# octanis_eps.net
KiCad netlist of a schematic drawn in EAGLE
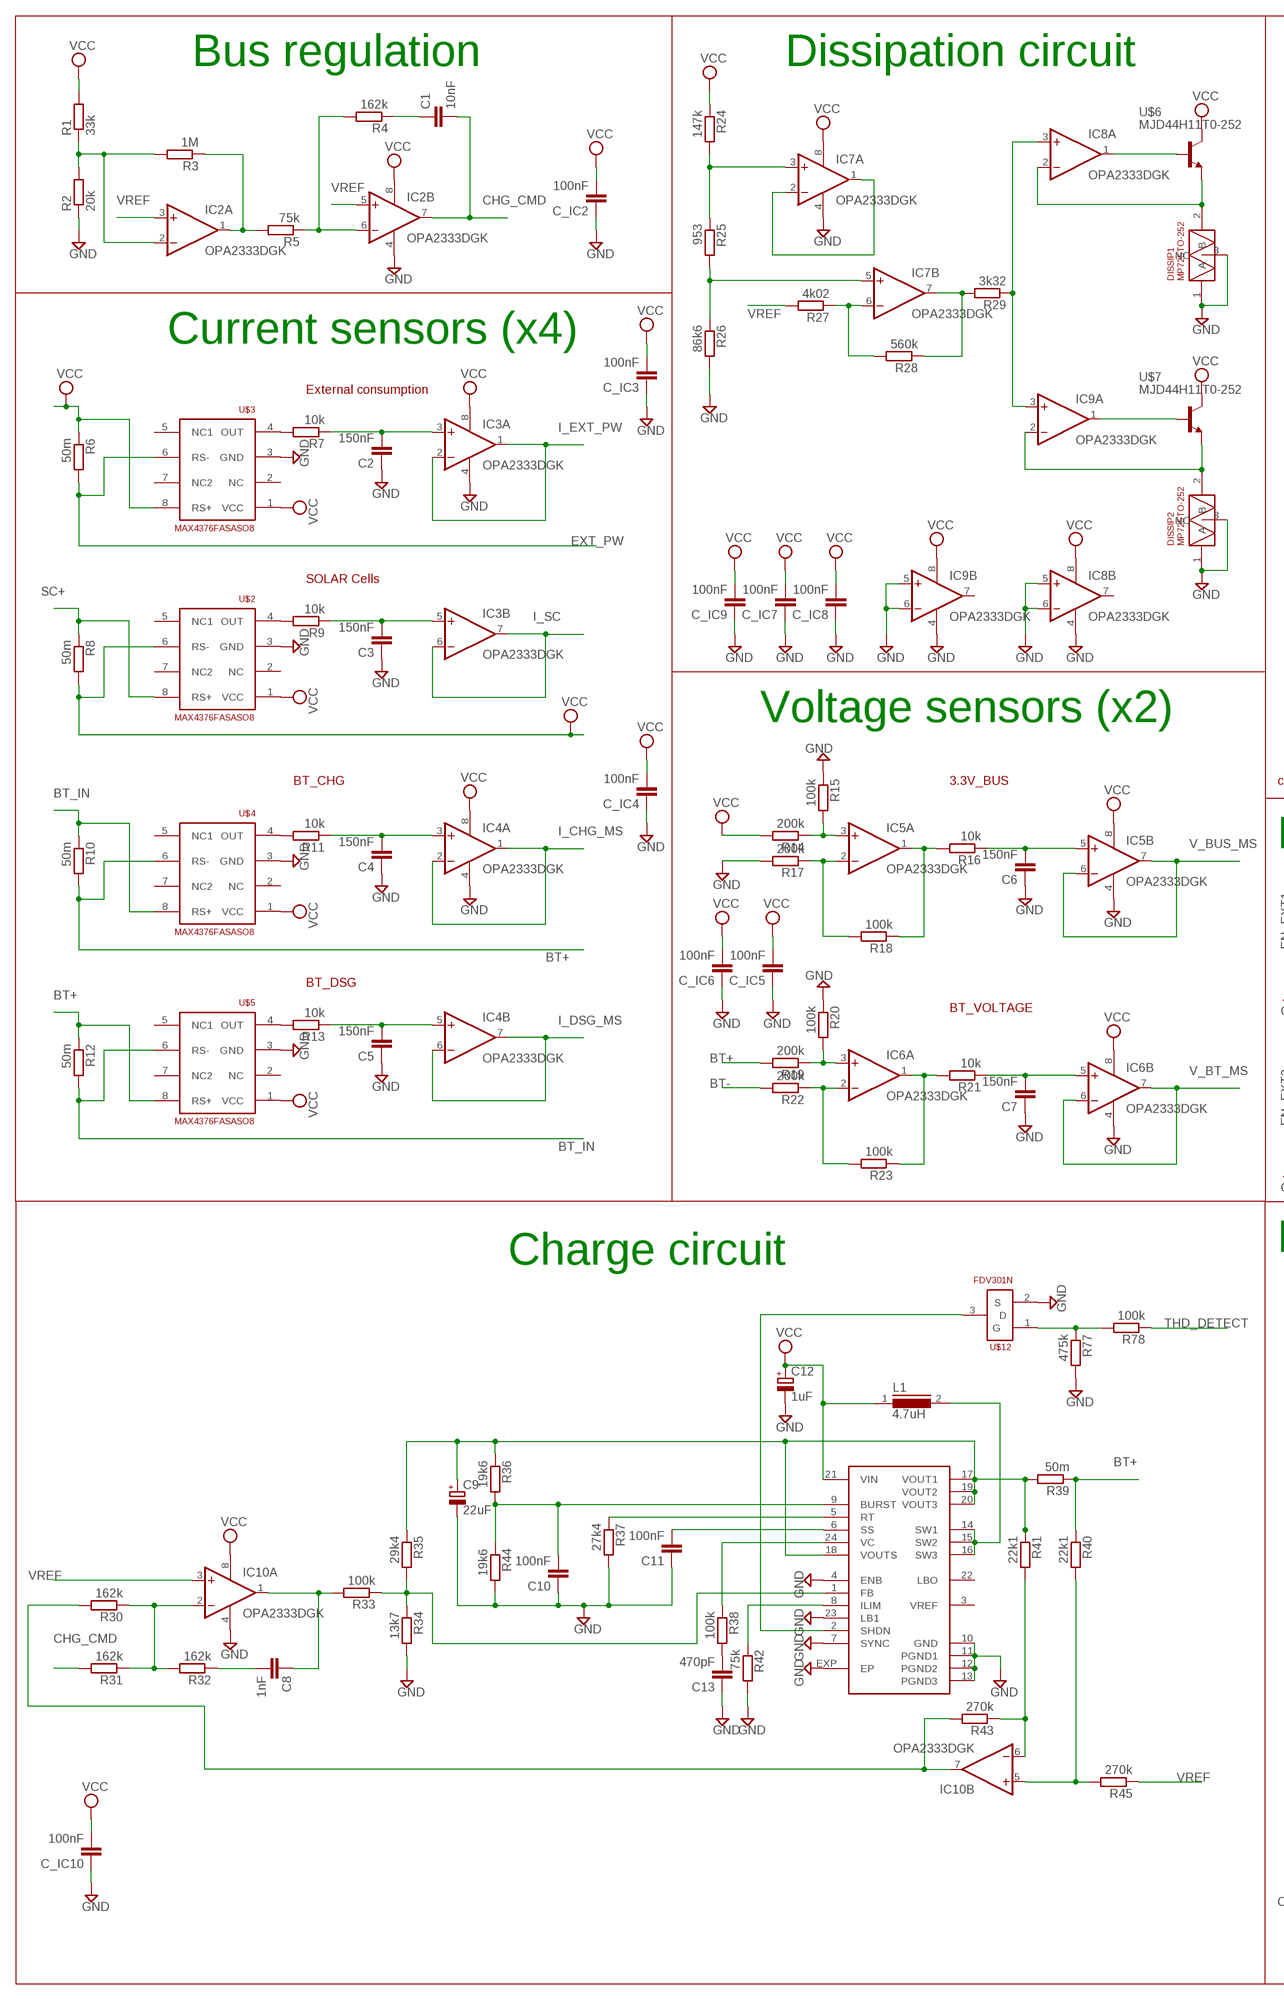
[diagram p0: schematic, sheet 1, part 1 of 2]
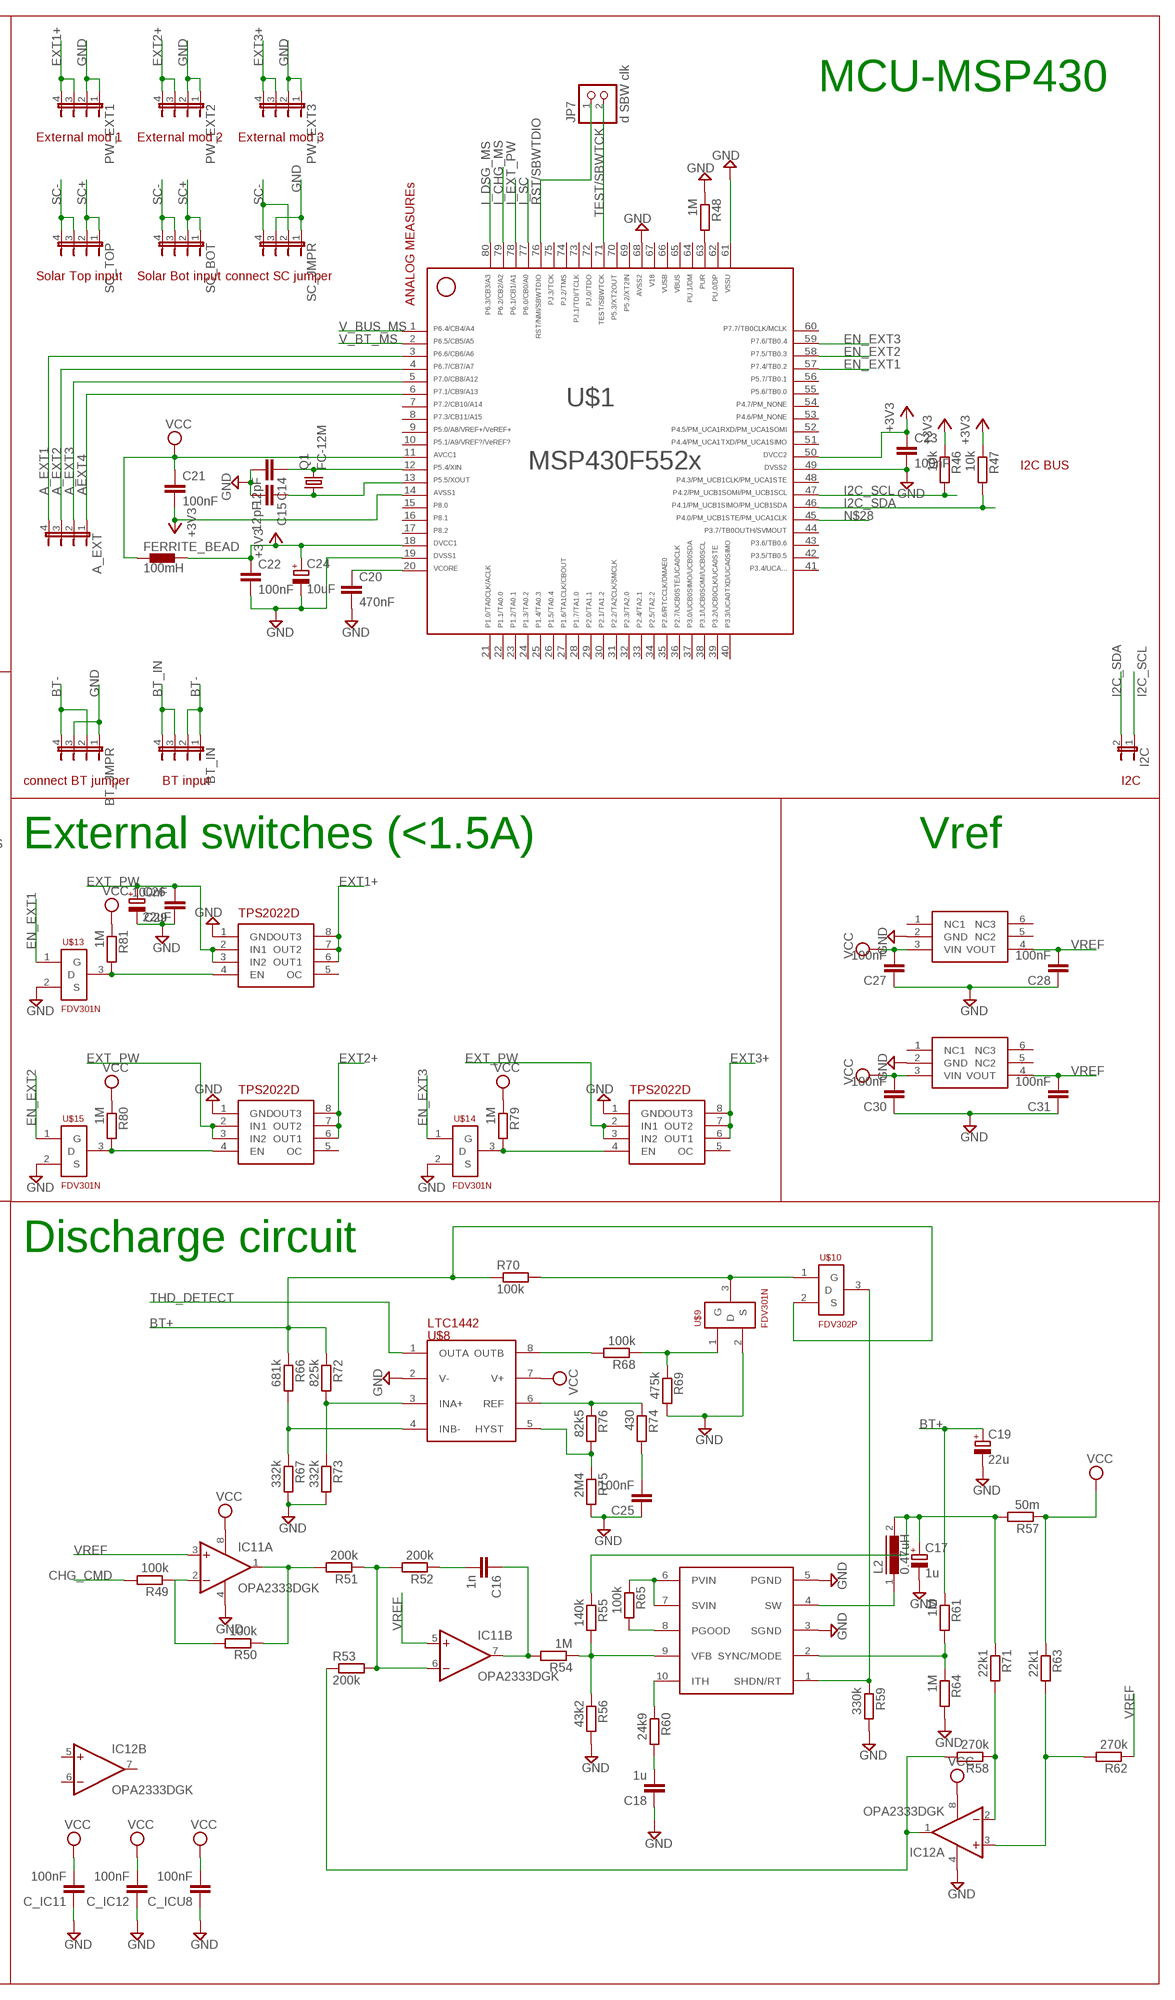
[diagram p1: schematic, sheet 1, part 2 of 2]

(export (version "E")
  (design (tool "Eeschema 10.0.6"))
  (components
    (comp (ref "A_EXT")
      (value "JP4E")
      (footprint "eagle-import:JP4")
      (libsource (lib "eagle-import") (part "JP4E"))
    )
    (comp (ref "BT_IN")
      (value "JP4E")
      (footprint "eagle-import:JP4")
      (libsource (lib "eagle-import") (part "JP4E"))
    )
    (comp (ref "BT_JMPR")
      (value "JP4E")
      (footprint "eagle-import:JP4")
      (libsource (lib "eagle-import") (part "JP4E"))
    )
    (comp (ref "C1")
      (value "10nF")
      (footprint "eagle-import:C0603")
      (libsource (lib "eagle-import") (part "C-EUC0603"))
    )
    (comp (ref "C2")
      (value "150nF")
      (footprint "eagle-import:C0603")
      (libsource (lib "eagle-import") (part "C-EUC0603"))
    )
    (comp (ref "C3")
      (value "150nF")
      (footprint "eagle-import:C0603")
      (libsource (lib "eagle-import") (part "C-EUC0603"))
    )
    (comp (ref "C4")
      (value "150nF")
      (footprint "eagle-import:C0603")
      (libsource (lib "eagle-import") (part "C-EUC0603"))
    )
    (comp (ref "C5")
      (value "150nF")
      (footprint "eagle-import:C0603")
      (libsource (lib "eagle-import") (part "C-EUC0603"))
    )
    (comp (ref "C6")
      (value "150nF")
      (footprint "eagle-import:C0603")
      (libsource (lib "eagle-import") (part "C-EUC0603"))
    )
    (comp (ref "C7")
      (value "150nF")
      (footprint "eagle-import:C0603")
      (libsource (lib "eagle-import") (part "C-EUC0603"))
    )
    (comp (ref "C8")
      (value "1nF")
      (footprint "eagle-import:C0603")
      (libsource (lib "eagle-import") (part "C-EUC0603"))
    )
    (comp (ref "C9")
      (value "22uF")
      (footprint "eagle-import:A_3216-18R")
      (libsource (lib "eagle-import") (part "CPOL-EUA/3216-18R"))
    )
    (comp (ref "C10")
      (value "100nF")
      (footprint "eagle-import:C0603")
      (libsource (lib "eagle-import") (part "C-EUC0603"))
    )
    (comp (ref "C11")
      (value "100nF")
      (footprint "eagle-import:C0603")
      (libsource (lib "eagle-import") (part "C-EUC0603"))
    )
    (comp (ref "C12")
      (value "1uF")
      (footprint "eagle-import:A_3216-18R")
      (libsource (lib "eagle-import") (part "CPOL-EUA/3216-18R"))
    )
    (comp (ref "C13")
      (value "470pF")
      (footprint "eagle-import:C0603")
      (libsource (lib "eagle-import") (part "C-EUC0603"))
    )
    (comp (ref "C14")
      (value "12pF")
      (footprint "eagle-import:C0603")
      (libsource (lib "eagle-import") (part "C-EUC0603"))
    )
    (comp (ref "C15")
      (value "12pF")
      (footprint "eagle-import:C0603")
      (libsource (lib "eagle-import") (part "C-EUC0603"))
    )
    (comp (ref "C16")
      (value "1n")
      (footprint "eagle-import:C0603")
      (libsource (lib "eagle-import") (part "C-EUC0603"))
    )
    (comp (ref "C17")
      (value "1u")
      (footprint "eagle-import:A_3216-18R")
      (libsource (lib "eagle-import") (part "CPOL-EUA/3216-18R"))
    )
    (comp (ref "C18")
      (value "1u")
      (footprint "eagle-import:C0603")
      (libsource (lib "eagle-import") (part "C-EUC0603"))
    )
    (comp (ref "C19")
      (value "22u")
      (footprint "eagle-import:A_3216-18R")
      (libsource (lib "eagle-import") (part "CPOL-EUA/3216-18R"))
    )
    (comp (ref "C20")
      (value "470nF")
      (footprint "eagle-import:C0603")
      (libsource (lib "eagle-import") (part "C-EUC0603"))
    )
    (comp (ref "C21")
      (value "100nF")
      (footprint "eagle-import:C0603")
      (libsource (lib "eagle-import") (part "C-EUC0603"))
    )
    (comp (ref "C22")
      (value "100nF")
      (footprint "eagle-import:C0603")
      (libsource (lib "eagle-import") (part "C-EUC0603"))
    )
    (comp (ref "C23")
      (value "100nF")
      (footprint "eagle-import:C0603")
      (libsource (lib "eagle-import") (part "C-EUC0603"))
    )
    (comp (ref "C24")
      (value "10uF")
      (footprint "eagle-import:A_3216-18R")
      (libsource (lib "eagle-import") (part "CPOL-EUA/3216-18R"))
    )
    (comp (ref "C25")
      (value "100nF")
      (footprint "eagle-import:C0603")
      (libsource (lib "eagle-import") (part "C-EUC0603"))
    )
    (comp (ref "C26")
      (value "22uF")
      (footprint "eagle-import:A_3216-18R")
      (libsource (lib "eagle-import") (part "CPOL-EUA/3216-18R"))
    )
    (comp (ref "C27")
      (value "100nF")
      (footprint "eagle-import:C0603")
      (libsource (lib "eagle-import") (part "C-EUC0603"))
    )
    (comp (ref "C28")
      (value "100nF")
      (footprint "eagle-import:C0603")
      (libsource (lib "eagle-import") (part "C-EUC0603"))
    )
    (comp (ref "C29")
      (value "100nF")
      (footprint "eagle-import:C0603")
      (libsource (lib "eagle-import") (part "C-EUC0603"))
    )
    (comp (ref "C30")
      (value "100nF")
      (footprint "eagle-import:C0603")
      (libsource (lib "eagle-import") (part "C-EUC0603"))
    )
    (comp (ref "C31")
      (value "100nF")
      (footprint "eagle-import:C0603")
      (libsource (lib "eagle-import") (part "C-EUC0603"))
    )
    (comp (ref "C_IC2")
      (value "100nF")
      (footprint "eagle-import:C0603")
      (libsource (lib "eagle-import") (part "C-EUC0603"))
    )
    (comp (ref "C_IC3")
      (value "100nF")
      (footprint "eagle-import:C0603")
      (libsource (lib "eagle-import") (part "C-EUC0603"))
    )
    (comp (ref "C_IC4")
      (value "100nF")
      (footprint "eagle-import:C0603")
      (libsource (lib "eagle-import") (part "C-EUC0603"))
    )
    (comp (ref "C_IC5")
      (value "100nF")
      (footprint "eagle-import:C0603")
      (libsource (lib "eagle-import") (part "C-EUC0603"))
    )
    (comp (ref "C_IC6")
      (value "100nF")
      (footprint "eagle-import:C0603")
      (libsource (lib "eagle-import") (part "C-EUC0603"))
    )
    (comp (ref "C_IC7")
      (value "100nF")
      (footprint "eagle-import:C0603")
      (libsource (lib "eagle-import") (part "C-EUC0603"))
    )
    (comp (ref "C_IC8")
      (value "100nF")
      (footprint "eagle-import:C0603")
      (libsource (lib "eagle-import") (part "C-EUC0603"))
    )
    (comp (ref "C_IC9")
      (value "100nF")
      (footprint "eagle-import:C0603")
      (libsource (lib "eagle-import") (part "C-EUC0603"))
    )
    (comp (ref "C_IC10")
      (value "100nF")
      (footprint "eagle-import:C0603")
      (libsource (lib "eagle-import") (part "C-EUC0603"))
    )
    (comp (ref "C_IC11")
      (value "100nF")
      (footprint "eagle-import:C0603")
      (libsource (lib "eagle-import") (part "C-EUC0603"))
    )
    (comp (ref "C_IC12")
      (value "100nF")
      (footprint "eagle-import:C0603")
      (libsource (lib "eagle-import") (part "C-EUC0603"))
    )
    (comp (ref "C_ICU8")
      (value "100nF")
      (footprint "eagle-import:C0603")
      (libsource (lib "eagle-import") (part "C-EUC0603"))
    )
    (comp (ref "DISSIP1")
      (value "MP725TO-252")
      (footprint "eagle-import:TO252")
      (libsource (lib "eagle-import") (part "MP725TO-252"))
    )
    (comp (ref "DISSIP2")
      (value "MP725TO-252")
      (footprint "eagle-import:TO252")
      (libsource (lib "eagle-import") (part "MP725TO-252"))
    )
    (comp (ref "FERRITE_BEAD")
      (value "100mH")
      (footprint "eagle-import:0402")
      (libsource (lib "eagle-import") (part "BLM15HD601SN1"))
    )
    (comp (ref "I2C")
      (value "JP1E")
      (footprint "eagle-import:JP1")
      (libsource (lib "eagle-import") (part "JP1E"))
    )
    (comp (ref "IC2")
      (value "OPA2333DGK")
      (footprint "eagle-import:MSOP08")
      (libsource (lib "eagle-import") (part "OPA2333DGK"))
    )
    (comp (ref "IC3")
      (value "OPA2333DGK")
      (footprint "eagle-import:MSOP08")
      (libsource (lib "eagle-import") (part "OPA2333DGK"))
    )
    (comp (ref "IC4")
      (value "OPA2333DGK")
      (footprint "eagle-import:MSOP08")
      (libsource (lib "eagle-import") (part "OPA2333DGK"))
    )
    (comp (ref "IC5")
      (value "OPA2333DGK")
      (footprint "eagle-import:MSOP08")
      (libsource (lib "eagle-import") (part "OPA2333DGK"))
    )
    (comp (ref "IC6")
      (value "OPA2333DGK")
      (footprint "eagle-import:MSOP08")
      (libsource (lib "eagle-import") (part "OPA2333DGK"))
    )
    (comp (ref "IC7")
      (value "OPA2333DGK")
      (footprint "eagle-import:MSOP08")
      (libsource (lib "eagle-import") (part "OPA2333DGK"))
    )
    (comp (ref "IC8")
      (value "OPA2333DGK")
      (footprint "eagle-import:MSOP08")
      (libsource (lib "eagle-import") (part "OPA2333DGK"))
    )
    (comp (ref "IC9")
      (value "OPA2333DGK")
      (footprint "eagle-import:MSOP08")
      (libsource (lib "eagle-import") (part "OPA2333DGK"))
    )
    (comp (ref "IC10")
      (value "OPA2333DGK")
      (footprint "eagle-import:MSOP08")
      (libsource (lib "eagle-import") (part "OPA2333DGK"))
    )
    (comp (ref "IC11")
      (value "OPA2333DGK")
      (footprint "eagle-import:MSOP08")
      (libsource (lib "eagle-import") (part "OPA2333DGK"))
    )
    (comp (ref "IC12")
      (value "OPA2333DGK")
      (footprint "eagle-import:MSOP08")
      (libsource (lib "eagle-import") (part "OPA2333DGK"))
    )
    (comp (ref "JP7")
      (value "d SBW clk")
      (footprint "eagle-import:1X02")
      (libsource (lib "eagle-import") (part "PINHD-1X2"))
    )
    (comp (ref "L1")
      (value "4.7uH")
      (footprint "eagle-import:DR73")
      (libsource (lib "eagle-import") (part "DR73"))
    )
    (comp (ref "L2")
      (value "0.47uH")
      (footprint "eagle-import:DR73")
      (libsource (lib "eagle-import") (part "DR73"))
    )
    (comp (ref "LTC3411")
      (value "LT3411")
      (footprint "eagle-import:MSOP10")
      (libsource (lib "eagle-import") (part "LT3411"))
    )
    (comp (ref "PW_EXT1")
      (value "JP4E")
      (footprint "eagle-import:JP4")
      (libsource (lib "eagle-import") (part "JP4E"))
    )
    (comp (ref "PW_EXT2")
      (value "JP4E")
      (footprint "eagle-import:JP4")
      (libsource (lib "eagle-import") (part "JP4E"))
    )
    (comp (ref "PW_EXT3")
      (value "JP4E")
      (footprint "eagle-import:JP4")
      (libsource (lib "eagle-import") (part "JP4E"))
    )
    (comp (ref "Q1")
      (value "FC-12M")
      (footprint "eagle-import:FC-12M")
      (libsource (lib "eagle-import") (part "FC-12M"))
    )
    (comp (ref "R1")
      (value "33k")
      (footprint "eagle-import:R0603")
      (libsource (lib "eagle-import") (part "R-EU_R0603"))
    )
    (comp (ref "R2")
      (value "20k")
      (footprint "eagle-import:R0603")
      (libsource (lib "eagle-import") (part "R-EU_R0603"))
    )
    (comp (ref "R3")
      (value "1M")
      (footprint "eagle-import:R0603")
      (libsource (lib "eagle-import") (part "R-EU_R0603"))
    )
    (comp (ref "R4")
      (value "162k")
      (footprint "eagle-import:R0603")
      (libsource (lib "eagle-import") (part "R-EU_R0603"))
    )
    (comp (ref "R5")
      (value "75k")
      (footprint "eagle-import:R0603")
      (libsource (lib "eagle-import") (part "R-EU_R0603"))
    )
    (comp (ref "R6")
      (value "50m")
      (footprint "eagle-import:R1206")
      (libsource (lib "eagle-import") (part "R-EU_R1206"))
    )
    (comp (ref "R7")
      (value "10k")
      (footprint "eagle-import:R0603")
      (libsource (lib "eagle-import") (part "R-EU_R0603"))
    )
    (comp (ref "R8")
      (value "50m")
      (footprint "eagle-import:R1206")
      (libsource (lib "eagle-import") (part "R-EU_R1206"))
    )
    (comp (ref "R9")
      (value "10k")
      (footprint "eagle-import:R0603")
      (libsource (lib "eagle-import") (part "R-EU_R0603"))
    )
    (comp (ref "R10")
      (value "50m")
      (footprint "eagle-import:R1206")
      (libsource (lib "eagle-import") (part "R-EU_R1206"))
    )
    (comp (ref "R11")
      (value "10k")
      (footprint "eagle-import:R0603")
      (libsource (lib "eagle-import") (part "R-EU_R0603"))
    )
    (comp (ref "R12")
      (value "50m")
      (footprint "eagle-import:R1206")
      (libsource (lib "eagle-import") (part "R-EU_R1206"))
    )
    (comp (ref "R13")
      (value "10k")
      (footprint "eagle-import:R0603")
      (libsource (lib "eagle-import") (part "R-EU_R0603"))
    )
    (comp (ref "R14")
      (value "200k")
      (footprint "eagle-import:R0603")
      (libsource (lib "eagle-import") (part "R-EU_R0603"))
    )
    (comp (ref "R15")
      (value "100k")
      (footprint "eagle-import:R0603")
      (libsource (lib "eagle-import") (part "R-EU_R0603"))
    )
    (comp (ref "R16")
      (value "10k")
      (footprint "eagle-import:R0603")
      (libsource (lib "eagle-import") (part "R-EU_R0603"))
    )
    (comp (ref "R17")
      (value "200k")
      (footprint "eagle-import:R0603")
      (libsource (lib "eagle-import") (part "R-EU_R0603"))
    )
    (comp (ref "R18")
      (value "100k")
      (footprint "eagle-import:R0603")
      (libsource (lib "eagle-import") (part "R-EU_R0603"))
    )
    (comp (ref "R19")
      (value "200k")
      (footprint "eagle-import:R0603")
      (libsource (lib "eagle-import") (part "R-EU_R0603"))
    )
    (comp (ref "R20")
      (value "100k")
      (footprint "eagle-import:R0603")
      (libsource (lib "eagle-import") (part "R-EU_R0603"))
    )
    (comp (ref "R21")
      (value "10k")
      (footprint "eagle-import:R0603")
      (libsource (lib "eagle-import") (part "R-EU_R0603"))
    )
    (comp (ref "R22")
      (value "200k")
      (footprint "eagle-import:R0603")
      (libsource (lib "eagle-import") (part "R-EU_R0603"))
    )
    (comp (ref "R23")
      (value "100k")
      (footprint "eagle-import:R0603")
      (libsource (lib "eagle-import") (part "R-EU_R0603"))
    )
    (comp (ref "R24")
      (value "147k")
      (footprint "eagle-import:R0603")
      (libsource (lib "eagle-import") (part "R-EU_R0603"))
    )
    (comp (ref "R25")
      (value "953")
      (footprint "eagle-import:R0603")
      (libsource (lib "eagle-import") (part "R-EU_R0603"))
    )
    (comp (ref "R26")
      (value "86k6")
      (footprint "eagle-import:R0603")
      (libsource (lib "eagle-import") (part "R-EU_R0603"))
    )
    (comp (ref "R27")
      (value "4k02")
      (footprint "eagle-import:R0603")
      (libsource (lib "eagle-import") (part "R-EU_R0603"))
    )
    (comp (ref "R28")
      (value "560k")
      (footprint "eagle-import:R0603")
      (libsource (lib "eagle-import") (part "R-EU_R0603"))
    )
    (comp (ref "R29")
      (value "3k32")
      (footprint "eagle-import:R0603")
      (libsource (lib "eagle-import") (part "R-EU_R0603"))
    )
    (comp (ref "R30")
      (value "162k")
      (footprint "eagle-import:R0603")
      (libsource (lib "eagle-import") (part "R-EU_R0603"))
    )
    (comp (ref "R31")
      (value "162k")
      (footprint "eagle-import:R0603")
      (libsource (lib "eagle-import") (part "R-EU_R0603"))
    )
    (comp (ref "R32")
      (value "162k")
      (footprint "eagle-import:R0603")
      (libsource (lib "eagle-import") (part "R-EU_R0603"))
    )
    (comp (ref "R33")
      (value "100k")
      (footprint "eagle-import:R0603")
      (libsource (lib "eagle-import") (part "R-EU_R0603"))
    )
    (comp (ref "R34")
      (value "13k7")
      (footprint "eagle-import:R0603")
      (libsource (lib "eagle-import") (part "R-EU_R0603"))
    )
    (comp (ref "R35")
      (value "29k4")
      (footprint "eagle-import:R0603")
      (libsource (lib "eagle-import") (part "R-EU_R0603"))
    )
    (comp (ref "R36")
      (value "19k6")
      (footprint "eagle-import:R0603")
      (libsource (lib "eagle-import") (part "R-EU_R0603"))
    )
    (comp (ref "R37")
      (value "27k4")
      (footprint "eagle-import:R0603")
      (libsource (lib "eagle-import") (part "R-EU_R0603"))
    )
    (comp (ref "R38")
      (value "100k")
      (footprint "eagle-import:R0603")
      (libsource (lib "eagle-import") (part "R-EU_R0603"))
    )
    (comp (ref "R39")
      (value "50m")
      (footprint "eagle-import:R1206")
      (libsource (lib "eagle-import") (part "R-EU_R1206"))
    )
    (comp (ref "R40")
      (value "22k1")
      (footprint "eagle-import:R0603")
      (libsource (lib "eagle-import") (part "R-EU_R0603"))
    )
    (comp (ref "R41")
      (value "22k1")
      (footprint "eagle-import:R0603")
      (libsource (lib "eagle-import") (part "R-EU_R0603"))
    )
    (comp (ref "R42")
      (value "75k")
      (footprint "eagle-import:R0603")
      (libsource (lib "eagle-import") (part "R-EU_R0603"))
    )
    (comp (ref "R43")
      (value "270k")
      (footprint "eagle-import:R0603")
      (libsource (lib "eagle-import") (part "R-EU_R0603"))
    )
    (comp (ref "R44")
      (value "19k6")
      (footprint "eagle-import:R0603")
      (libsource (lib "eagle-import") (part "R-EU_R0603"))
    )
    (comp (ref "R45")
      (value "270k")
      (footprint "eagle-import:R0603")
      (libsource (lib "eagle-import") (part "R-EU_R0603"))
    )
    (comp (ref "R46")
      (value "10k")
      (footprint "eagle-import:R0603")
      (libsource (lib "eagle-import") (part "R-EU_R0603"))
    )
    (comp (ref "R47")
      (value "10k")
      (footprint "eagle-import:R0603")
      (libsource (lib "eagle-import") (part "R-EU_R0603"))
    )
    (comp (ref "R48")
      (value "1M")
      (footprint "eagle-import:R0603")
      (libsource (lib "eagle-import") (part "R-EU_R0603"))
    )
    (comp (ref "R49")
      (value "100k")
      (footprint "eagle-import:R0603")
      (libsource (lib "eagle-import") (part "R-EU_R0603"))
    )
    (comp (ref "R50")
      (value "100k")
      (footprint "eagle-import:R0603")
      (libsource (lib "eagle-import") (part "R-EU_R0603"))
    )
    (comp (ref "R51")
      (value "200k")
      (footprint "eagle-import:R0603")
      (libsource (lib "eagle-import") (part "R-EU_R0603"))
    )
    (comp (ref "R52")
      (value "200k")
      (footprint "eagle-import:R0603")
      (libsource (lib "eagle-import") (part "R-EU_R0603"))
    )
    (comp (ref "R53")
      (value "200k")
      (footprint "eagle-import:R0603")
      (libsource (lib "eagle-import") (part "R-EU_R0603"))
    )
    (comp (ref "R54")
      (value "1M")
      (footprint "eagle-import:R0603")
      (libsource (lib "eagle-import") (part "R-EU_R0603"))
    )
    (comp (ref "R55")
      (value "140k")
      (footprint "eagle-import:R0603")
      (libsource (lib "eagle-import") (part "R-EU_R0603"))
    )
    (comp (ref "R56")
      (value "43k2")
      (footprint "eagle-import:R0603")
      (libsource (lib "eagle-import") (part "R-EU_R0603"))
    )
    (comp (ref "R57")
      (value "50m")
      (footprint "eagle-import:R1206")
      (libsource (lib "eagle-import") (part "R-EU_R1206"))
    )
    (comp (ref "R58")
      (value "270k")
      (footprint "eagle-import:R0603")
      (libsource (lib "eagle-import") (part "R-EU_R0603"))
    )
    (comp (ref "R59")
      (value "330k")
      (footprint "eagle-import:R0603")
      (libsource (lib "eagle-import") (part "R-EU_R0603"))
    )
    (comp (ref "R60")
      (value "24k9")
      (footprint "eagle-import:R0603")
      (libsource (lib "eagle-import") (part "R-EU_R0603"))
    )
    (comp (ref "R61")
      (value "1M")
      (footprint "eagle-import:R0603")
      (libsource (lib "eagle-import") (part "R-EU_R0603"))
    )
    (comp (ref "R62")
      (value "270k")
      (footprint "eagle-import:R0603")
      (libsource (lib "eagle-import") (part "R-EU_R0603"))
    )
    (comp (ref "R63")
      (value "22k1")
      (footprint "eagle-import:R0603")
      (libsource (lib "eagle-import") (part "R-EU_R0603"))
    )
    (comp (ref "R64")
      (value "1M")
      (footprint "eagle-import:R0603")
      (libsource (lib "eagle-import") (part "R-EU_R0603"))
    )
    (comp (ref "R65")
      (value "100k")
      (footprint "eagle-import:R0603")
      (libsource (lib "eagle-import") (part "R-EU_R0603"))
    )
    (comp (ref "R66")
      (value "681k")
      (footprint "eagle-import:R0603")
      (libsource (lib "eagle-import") (part "R-EU_R0603"))
    )
    (comp (ref "R67")
      (value "332k")
      (footprint "eagle-import:R0603")
      (libsource (lib "eagle-import") (part "R-EU_R0603"))
    )
    (comp (ref "R68")
      (value "100k")
      (footprint "eagle-import:R0603")
      (libsource (lib "eagle-import") (part "R-EU_R0603"))
    )
    (comp (ref "R69")
      (value "475k")
      (footprint "eagle-import:R0603")
      (libsource (lib "eagle-import") (part "R-EU_R0603"))
    )
    (comp (ref "R70")
      (value "100k")
      (footprint "eagle-import:R0603")
      (libsource (lib "eagle-import") (part "R-EU_R0603"))
    )
    (comp (ref "R71")
      (value "22k1")
      (footprint "eagle-import:R0603")
      (libsource (lib "eagle-import") (part "R-EU_R0603"))
    )
    (comp (ref "R72")
      (value "825k")
      (footprint "eagle-import:R0603")
      (libsource (lib "eagle-import") (part "R-EU_R0603"))
    )
    (comp (ref "R73")
      (value "332k")
      (footprint "eagle-import:R0603")
      (libsource (lib "eagle-import") (part "R-EU_R0603"))
    )
    (comp (ref "R74")
      (value "430")
      (footprint "eagle-import:R0603")
      (libsource (lib "eagle-import") (part "R-EU_R0603"))
    )
    (comp (ref "R75")
      (value "2M4")
      (footprint "eagle-import:R0603")
      (libsource (lib "eagle-import") (part "R-EU_R0603"))
    )
    (comp (ref "R76")
      (value "82k5")
      (footprint "eagle-import:R0603")
      (libsource (lib "eagle-import") (part "R-EU_R0603"))
    )
    (comp (ref "R77")
      (value "475k")
      (footprint "eagle-import:R0603")
      (libsource (lib "eagle-import") (part "R-EU_R0603"))
    )
    (comp (ref "R78")
      (value "100k")
      (footprint "eagle-import:R0603")
      (libsource (lib "eagle-import") (part "R-EU_R0603"))
    )
    (comp (ref "R79")
      (value "1M")
      (footprint "eagle-import:R0603")
      (libsource (lib "eagle-import") (part "R-EU_R0603"))
    )
    (comp (ref "R80")
      (value "1M")
      (footprint "eagle-import:R0603")
      (libsource (lib "eagle-import") (part "R-EU_R0603"))
    )
    (comp (ref "R81")
      (value "1M")
      (footprint "eagle-import:R0603")
      (libsource (lib "eagle-import") (part "R-EU_R0603"))
    )
    (comp (ref "SC_BOT")
      (value "JP4E")
      (footprint "eagle-import:JP4")
      (libsource (lib "eagle-import") (part "JP4E"))
    )
    (comp (ref "SC_JMPR")
      (value "JP4E")
      (footprint "eagle-import:JP4")
      (libsource (lib "eagle-import") (part "JP4E"))
    )
    (comp (ref "SC_TOP")
      (value "JP4E")
      (footprint "eagle-import:JP4")
      (libsource (lib "eagle-import") (part "JP4E"))
    )
    (comp (ref "U$1")
      (value "F552X---PN80")
      (footprint "eagle-import:PN80")
      (libsource (lib "eagle-import") (part "F552X---PN80"))
    )
    (comp (ref "U$2")
      (value "MAX4376FASASO8")
      (footprint "eagle-import:SO8")
      (libsource (lib "eagle-import") (part "MAX4376FASASO8"))
    )
    (comp (ref "U$3")
      (value "MAX4376FASASO8")
      (footprint "eagle-import:SO8")
      (libsource (lib "eagle-import") (part "MAX4376FASASO8"))
    )
    (comp (ref "U$4")
      (value "MAX4376FASASO8")
      (footprint "eagle-import:SO8")
      (libsource (lib "eagle-import") (part "MAX4376FASASO8"))
    )
    (comp (ref "U$5")
      (value "MAX4376FASASO8")
      (footprint "eagle-import:SO8")
      (libsource (lib "eagle-import") (part "MAX4376FASASO8"))
    )
    (comp (ref "U$6")
      (value "MJD44H11T0-252")
      (footprint "eagle-import:TO252")
      (libsource (lib "eagle-import") (part "MJD44H11T0-252"))
    )
    (comp (ref "U$7")
      (value "MJD44H11T0-252")
      (footprint "eagle-import:TO252")
      (libsource (lib "eagle-import") (part "MJD44H11T0-252"))
    )
    (comp (ref "U$8")
      (value "LTC1442")
      (footprint "eagle-import:SO8")
      (libsource (lib "eagle-import") (part "LTC1442"))
    )
    (comp (ref "U$9")
      (value "FDV301N")
      (footprint "eagle-import:SOT23")
      (libsource (lib "eagle-import") (part "FDV301N"))
    )
    (comp (ref "U$10")
      (value "FDV302P")
      (footprint "eagle-import:SOT23")
      (libsource (lib "eagle-import") (part "FDV302P"))
    )
    (comp (ref "U$11")
      (value "LTC3421")
      (footprint "eagle-import:QFN24")
      (libsource (lib "eagle-import") (part "LTC3421"))
    )
    (comp (ref "U$12")
      (value "FDV301N")
      (footprint "eagle-import:SOT23")
      (libsource (lib "eagle-import") (part "FDV301N"))
    )
    (comp (ref "U$13")
      (value "FDV301N")
      (footprint "eagle-import:SOT23")
      (libsource (lib "eagle-import") (part "FDV301N"))
    )
    (comp (ref "U$14")
      (value "FDV301N")
      (footprint "eagle-import:SOT23")
      (libsource (lib "eagle-import") (part "FDV301N"))
    )
    (comp (ref "U$15")
      (value "FDV301N")
      (footprint "eagle-import:SOT23")
      (libsource (lib "eagle-import") (part "FDV301N"))
    )
    (comp (ref "U$16")
      (value "TPS2022D")
      (footprint "eagle-import:SO8")
      (libsource (lib "eagle-import") (part "TPS2022D"))
    )
    (comp (ref "U$17")
      (value "TPS2022D")
      (footprint "eagle-import:SO8")
      (libsource (lib "eagle-import") (part "TPS2022D"))
    )
    (comp (ref "U$18")
      (value "TPS2022D")
      (footprint "eagle-import:SO8")
      (libsource (lib "eagle-import") (part "TPS2022D"))
    )
    (comp (ref "U$19")
      (value "ADR127B")
      (footprint "eagle-import:TSOT23-6")
      (libsource (lib "eagle-import") (part "ADR127B"))
    )
    (comp (ref "U$20")
      (value "ADR127B")
      (footprint "eagle-import:TSOT23-6")
      (libsource (lib "eagle-import") (part "ADR127B"))
    )
  )
  (nets
    (net (code "1") (name "+3V3") (class "Default")
      (node (ref "C21") (pin "2") (pinfunction "2_2") (pintype "passive"))
      (node (ref "C22") (pin "1") (pinfunction "1_1") (pintype "passive"))
      (node (ref "C23") (pin "1") (pinfunction "1_1") (pintype "passive"))
      (node (ref "C24") (pin "+") (pinfunction "+_+") (pintype "passive"))
      (node (ref "FERRITE_BEAD") (pin "2") (pinfunction "2_2") (pintype "passive"))
      (node (ref "R46") (pin "1") (pinfunction "1_1") (pintype "passive"))
      (node (ref "R47") (pin "1") (pinfunction "1_1") (pintype "passive"))
      (node (ref "U$1") (pin "14") (pinfunction "14_14") (pintype "power_in"))
      (node (ref "U$1") (pin "18") (pinfunction "18_18") (pintype "power_in"))
      (node (ref "U$1") (pin "50") (pinfunction "50_50") (pintype "power_in"))
    )
    (net (code "2") (name "/65") (class "Default")
      (node (ref "U$1") (pin "65") (pinfunction "65_65") (pintype "power_in"))
    )
    (net (code "3") (name "/66") (class "Default")
      (node (ref "U$1") (pin "66") (pinfunction "66_66") (pintype "power_in"))
    )
    (net (code "4") (name "/67") (class "Default")
      (node (ref "U$1") (pin "67") (pinfunction "67_67") (pintype "power_in"))
    )
    (net (code "5") (name "/AEXT4") (class "Default")
      (node (ref "A_EXT") (pin "1") (pinfunction "1_1") (pintype "passive"))
      (node (ref "U$1") (pin "6") (pinfunction "6_6") (pintype "bidirectional"))
    )
    (net (code "6") (name "/A_EXT1") (class "Default")
      (node (ref "A_EXT") (pin "4") (pinfunction "4_4") (pintype "passive"))
      (node (ref "U$1") (pin "3") (pinfunction "3_3") (pintype "bidirectional"))
    )
    (net (code "7") (name "/A_EXT2") (class "Default")
      (node (ref "A_EXT") (pin "3") (pinfunction "3_3") (pintype "passive"))
      (node (ref "U$1") (pin "4") (pinfunction "4_4") (pintype "bidirectional"))
    )
    (net (code "8") (name "/A_EXT3") (class "Default")
      (node (ref "A_EXT") (pin "2") (pinfunction "2_2") (pintype "passive"))
      (node (ref "U$1") (pin "5") (pinfunction "5_5") (pintype "bidirectional"))
    )
    (net (code "9") (name "/BT+") (class "Default")
      (node (ref "C19") (pin "+") (pinfunction "+_+") (pintype "passive"))
      (node (ref "R10") (pin "2") (pinfunction "2_2") (pintype "passive"))
      (node (ref "R12") (pin "1") (pinfunction "1_1") (pintype "passive"))
      (node (ref "R19") (pin "2") (pinfunction "2_2") (pintype "passive"))
      (node (ref "R39") (pin "1") (pinfunction "1_1") (pintype "passive"))
      (node (ref "R40") (pin "1") (pinfunction "1_1") (pintype "passive"))
      (node (ref "R61") (pin "1") (pinfunction "1_1") (pintype "passive"))
      (node (ref "R66") (pin "1") (pinfunction "1_1") (pintype "passive"))
      (node (ref "R70") (pin "1") (pinfunction "1_1") (pintype "passive"))
      (node (ref "R72") (pin "1") (pinfunction "1_1") (pintype "passive"))
      (node (ref "U$10") (pin "2") (pinfunction "S_2") (pintype "bidirectional"))
      (node (ref "U$4") (pin "6") (pinfunction "RS-_6") (pintype "bidirectional"))
      (node (ref "U$5") (pin "8") (pinfunction "RS+_8") (pintype "bidirectional"))
    )
    (net (code "10") (name "/BT-") (class "Default")
      (node (ref "BT_IN") (pin "1") (pinfunction "1_1") (pintype "passive"))
      (node (ref "BT_IN") (pin "2") (pinfunction "2_2") (pintype "passive"))
      (node (ref "BT_JMPR") (pin "2") (pinfunction "2_2") (pintype "passive"))
      (node (ref "BT_JMPR") (pin "4") (pinfunction "4_4") (pintype "passive"))
      (node (ref "R22") (pin "2") (pinfunction "2_2") (pintype "passive"))
    )
    (net (code "11") (name "/BT_IN") (class "Default")
      (node (ref "BT_IN") (pin "3") (pinfunction "3_3") (pintype "passive"))
      (node (ref "BT_IN") (pin "4") (pinfunction "4_4") (pintype "passive"))
      (node (ref "R10") (pin "1") (pinfunction "1_1") (pintype "passive"))
      (node (ref "R12") (pin "2") (pinfunction "2_2") (pintype "passive"))
      (node (ref "U$4") (pin "8") (pinfunction "RS+_8") (pintype "bidirectional"))
      (node (ref "U$5") (pin "6") (pinfunction "RS-_6") (pintype "bidirectional"))
    )
    (net (code "12") (name "/CHG_CMD") (class "Default")
      (node (ref "C1") (pin "2") (pinfunction "2_2") (pintype "passive"))
      (node (ref "IC2") (pin "7") (pinfunction "OUT_7") (pintype "output"))
      (node (ref "R31") (pin "2") (pinfunction "2_2") (pintype "passive"))
      (node (ref "R49") (pin "2") (pinfunction "2_2") (pintype "passive"))
    )
    (net (code "13") (name "/EN_EXT1") (class "Default")
      (node (ref "U$1") (pin "57") (pinfunction "57_57") (pintype "bidirectional"))
      (node (ref "U$13") (pin "1") (pinfunction "G_1") (pintype "bidirectional"))
    )
    (net (code "14") (name "/EN_EXT2") (class "Default")
      (node (ref "U$1") (pin "58") (pinfunction "58_58") (pintype "bidirectional"))
      (node (ref "U$15") (pin "1") (pinfunction "G_1") (pintype "bidirectional"))
    )
    (net (code "15") (name "/EN_EXT3") (class "Default")
      (node (ref "U$1") (pin "59") (pinfunction "59_59") (pintype "bidirectional"))
      (node (ref "U$14") (pin "1") (pinfunction "G_1") (pintype "bidirectional"))
    )
    (net (code "16") (name "/EXT1+") (class "Default")
      (node (ref "PW_EXT1") (pin "3") (pinfunction "3_3") (pintype "passive"))
      (node (ref "PW_EXT1") (pin "4") (pinfunction "4_4") (pintype "passive"))
      (node (ref "U$16") (pin "6") (pinfunction "OUT1_6") (pintype "bidirectional"))
      (node (ref "U$16") (pin "7") (pinfunction "OUT2_7") (pintype "bidirectional"))
      (node (ref "U$16") (pin "8") (pinfunction "OUT3_8") (pintype "bidirectional"))
    )
    (net (code "17") (name "/EXT2+") (class "Default")
      (node (ref "PW_EXT2") (pin "3") (pinfunction "3_3") (pintype "passive"))
      (node (ref "PW_EXT2") (pin "4") (pinfunction "4_4") (pintype "passive"))
      (node (ref "U$17") (pin "6") (pinfunction "OUT1_6") (pintype "bidirectional"))
      (node (ref "U$17") (pin "7") (pinfunction "OUT2_7") (pintype "bidirectional"))
      (node (ref "U$17") (pin "8") (pinfunction "OUT3_8") (pintype "bidirectional"))
    )
    (net (code "18") (name "/EXT3+") (class "Default")
      (node (ref "PW_EXT3") (pin "3") (pinfunction "3_3") (pintype "passive"))
      (node (ref "PW_EXT3") (pin "4") (pinfunction "4_4") (pintype "passive"))
      (node (ref "U$18") (pin "6") (pinfunction "OUT1_6") (pintype "bidirectional"))
      (node (ref "U$18") (pin "7") (pinfunction "OUT2_7") (pintype "bidirectional"))
      (node (ref "U$18") (pin "8") (pinfunction "OUT3_8") (pintype "bidirectional"))
    )
    (net (code "19") (name "/EXT_PW") (class "Default")
      (node (ref "C26") (pin "+") (pinfunction "+_+") (pintype "passive"))
      (node (ref "C29") (pin "2") (pinfunction "2_2") (pintype "passive"))
      (node (ref "R6") (pin "2") (pinfunction "2_2") (pintype "passive"))
      (node (ref "U$16") (pin "2") (pinfunction "IN1_2") (pintype "bidirectional"))
      (node (ref "U$16") (pin "3") (pinfunction "IN2_3") (pintype "bidirectional"))
      (node (ref "U$17") (pin "2") (pinfunction "IN1_2") (pintype "bidirectional"))
      (node (ref "U$17") (pin "3") (pinfunction "IN2_3") (pintype "bidirectional"))
      (node (ref "U$18") (pin "2") (pinfunction "IN1_2") (pintype "bidirectional"))
      (node (ref "U$18") (pin "3") (pinfunction "IN2_3") (pintype "bidirectional"))
      (node (ref "U$3") (pin "6") (pinfunction "RS-_6") (pintype "bidirectional"))
    )
    (net (code "20") (name "/I2C_SCL") (class "Default")
      (node (ref "I2C") (pin "1") (pinfunction "1_1") (pintype "passive"))
      (node (ref "R46") (pin "2") (pinfunction "2_2") (pintype "passive"))
      (node (ref "U$1") (pin "47") (pinfunction "47_47") (pintype "bidirectional"))
    )
    (net (code "21") (name "/I2C_SDA") (class "Default")
      (node (ref "I2C") (pin "2") (pinfunction "2_2") (pintype "passive"))
      (node (ref "R47") (pin "2") (pinfunction "2_2") (pintype "passive"))
      (node (ref "U$1") (pin "46") (pinfunction "46_46") (pintype "bidirectional"))
    )
    (net (code "22") (name "/I_CHG_MS") (class "Default")
      (node (ref "IC4") (pin "1") (pinfunction "OUT_1") (pintype "output"))
      (node (ref "IC4") (pin "2") (pinfunction "-IN_2") (pintype "input"))
      (node (ref "U$1") (pin "79") (pinfunction "79_79") (pintype "bidirectional"))
    )
    (net (code "23") (name "/I_DSG_MS") (class "Default")
      (node (ref "IC4") (pin "6") (pinfunction "-IN_6") (pintype "input"))
      (node (ref "IC4") (pin "7") (pinfunction "OUT_7") (pintype "output"))
      (node (ref "U$1") (pin "80") (pinfunction "80_80") (pintype "bidirectional"))
    )
    (net (code "24") (name "/I_EXT_PW") (class "Default")
      (node (ref "IC3") (pin "1") (pinfunction "OUT_1") (pintype "output"))
      (node (ref "IC3") (pin "2") (pinfunction "-IN_2") (pintype "input"))
      (node (ref "U$1") (pin "78") (pinfunction "78_78") (pintype "bidirectional"))
    )
    (net (code "25") (name "/I_SC") (class "Default")
      (node (ref "IC3") (pin "6") (pinfunction "-IN_6") (pintype "input"))
      (node (ref "IC3") (pin "7") (pinfunction "OUT_7") (pintype "output"))
      (node (ref "U$1") (pin "77") (pinfunction "77_77") (pintype "bidirectional"))
    )
    (net (code "26") (name "/N$28") (class "Default")
      (node (ref "U$1") (pin "45") (pinfunction "45_45") (pintype "bidirectional"))
    )
    (net (code "27") (name "/RST{slash}SBWTDIO") (class "Default")
      (node (ref "JP7") (pin "1") (pinfunction "1_1") (pintype "passive"))
      (node (ref "U$1") (pin "76") (pinfunction "76_76") (pintype "bidirectional"))
    )
    (net (code "28") (name "/SC+") (class "Default")
      (node (ref "R8") (pin "1") (pinfunction "1_1") (pintype "passive"))
      (node (ref "SC_BOT") (pin "1") (pinfunction "1_1") (pintype "passive"))
      (node (ref "SC_BOT") (pin "2") (pinfunction "2_2") (pintype "passive"))
      (node (ref "SC_TOP") (pin "1") (pinfunction "1_1") (pintype "passive"))
      (node (ref "SC_TOP") (pin "2") (pinfunction "2_2") (pintype "passive"))
      (node (ref "U$2") (pin "8") (pinfunction "RS+_8") (pintype "bidirectional"))
    )
    (net (code "29") (name "/SC-") (class "Default")
      (node (ref "SC_BOT") (pin "3") (pinfunction "3_3") (pintype "passive"))
      (node (ref "SC_BOT") (pin "4") (pinfunction "4_4") (pintype "passive"))
      (node (ref "SC_JMPR") (pin "2") (pinfunction "2_2") (pintype "passive"))
      (node (ref "SC_JMPR") (pin "4") (pinfunction "4_4") (pintype "passive"))
      (node (ref "SC_TOP") (pin "3") (pinfunction "3_3") (pintype "passive"))
      (node (ref "SC_TOP") (pin "4") (pinfunction "4_4") (pintype "passive"))
    )
    (net (code "30") (name "/TEST{slash}SBWTCK") (class "Default")
      (node (ref "JP7") (pin "2") (pinfunction "2_2") (pintype "passive"))
      (node (ref "U$1") (pin "71") (pinfunction "71_71") (pintype "input"))
    )
    (net (code "31") (name "/THD_DETECT") (class "Default")
      (node (ref "R78") (pin "1") (pinfunction "1_1") (pintype "passive"))
      (node (ref "U$8") (pin "1") (pinfunction "OUTA_1") (pintype "bidirectional"))
    )
    (net (code "32") (name "/VREF") (class "Default")
      (node (ref "C28") (pin "2") (pinfunction "2_2") (pintype "passive"))
      (node (ref "C31") (pin "2") (pinfunction "2_2") (pintype "passive"))
      (node (ref "IC10") (pin "3") (pinfunction "+IN_3") (pintype "input"))
      (node (ref "IC11") (pin "3") (pinfunction "+IN_3") (pintype "input"))
      (node (ref "IC11") (pin "5") (pinfunction "+IN_5") (pintype "input"))
      (node (ref "IC2") (pin "3") (pinfunction "+IN_3") (pintype "input"))
      (node (ref "IC2") (pin "5") (pinfunction "+IN_5") (pintype "input"))
      (node (ref "R27") (pin "2") (pinfunction "2_2") (pintype "passive"))
      (node (ref "R45") (pin "1") (pinfunction "1_1") (pintype "passive"))
      (node (ref "R62") (pin "1") (pinfunction "1_1") (pintype "passive"))
      (node (ref "U$19") (pin "4") (pinfunction "VOUT_4") (pintype "bidirectional"))
      (node (ref "U$20") (pin "4") (pinfunction "VOUT_4") (pintype "bidirectional"))
    )
    (net (code "33") (name "/V_BT_MS") (class "Default")
      (node (ref "IC6") (pin "6") (pinfunction "-IN_6") (pintype "input"))
      (node (ref "IC6") (pin "7") (pinfunction "OUT_7") (pintype "output"))
      (node (ref "U$1") (pin "2") (pinfunction "2_2") (pintype "bidirectional"))
    )
    (net (code "34") (name "/V_BUS_MS") (class "Default")
      (node (ref "IC5") (pin "6") (pinfunction "-IN_6") (pintype "input"))
      (node (ref "IC5") (pin "7") (pinfunction "OUT_7") (pintype "output"))
      (node (ref "U$1") (pin "1") (pinfunction "1_1") (pintype "bidirectional"))
    )
    (net (code "35") (name "GND") (class "Default")
      (node (ref "BT_JMPR") (pin "1") (pinfunction "1_1") (pintype "passive"))
      (node (ref "BT_JMPR") (pin "3") (pinfunction "3_3") (pintype "passive"))
      (node (ref "C10") (pin "1") (pinfunction "1_1") (pintype "passive"))
      (node (ref "C11") (pin "1") (pinfunction "1_1") (pintype "passive"))
      (node (ref "C12") (pin "-") (pinfunction "-_-") (pintype "passive"))
      (node (ref "C13") (pin "1") (pinfunction "1_1") (pintype "passive"))
      (node (ref "C14") (pin "2") (pinfunction "2_2") (pintype "passive"))
      (node (ref "C15") (pin "2") (pinfunction "2_2") (pintype "passive"))
      (node (ref "C17") (pin "-") (pinfunction "-_-") (pintype "passive"))
      (node (ref "C18") (pin "1") (pinfunction "1_1") (pintype "passive"))
      (node (ref "C19") (pin "-") (pinfunction "-_-") (pintype "passive"))
      (node (ref "C2") (pin "1") (pinfunction "1_1") (pintype "passive"))
      (node (ref "C20") (pin "2") (pinfunction "2_2") (pintype "passive"))
      (node (ref "C22") (pin "2") (pinfunction "2_2") (pintype "passive"))
      (node (ref "C23") (pin "2") (pinfunction "2_2") (pintype "passive"))
      (node (ref "C24") (pin "-") (pinfunction "-_-") (pintype "passive"))
      (node (ref "C25") (pin "1") (pinfunction "1_1") (pintype "passive"))
      (node (ref "C26") (pin "-") (pinfunction "-_-") (pintype "passive"))
      (node (ref "C27") (pin "1") (pinfunction "1_1") (pintype "passive"))
      (node (ref "C28") (pin "1") (pinfunction "1_1") (pintype "passive"))
      (node (ref "C29") (pin "1") (pinfunction "1_1") (pintype "passive"))
      (node (ref "C3") (pin "1") (pinfunction "1_1") (pintype "passive"))
      (node (ref "C30") (pin "1") (pinfunction "1_1") (pintype "passive"))
      (node (ref "C31") (pin "1") (pinfunction "1_1") (pintype "passive"))
      (node (ref "C4") (pin "1") (pinfunction "1_1") (pintype "passive"))
      (node (ref "C5") (pin "1") (pinfunction "1_1") (pintype "passive"))
      (node (ref "C6") (pin "1") (pinfunction "1_1") (pintype "passive"))
      (node (ref "C7") (pin "1") (pinfunction "1_1") (pintype "passive"))
      (node (ref "C9") (pin "-") (pinfunction "-_-") (pintype "passive"))
      (node (ref "C_IC10") (pin "1") (pinfunction "1_1") (pintype "passive"))
      (node (ref "C_IC11") (pin "1") (pinfunction "1_1") (pintype "passive"))
      (node (ref "C_IC12") (pin "1") (pinfunction "1_1") (pintype "passive"))
      (node (ref "C_IC2") (pin "1") (pinfunction "1_1") (pintype "passive"))
      (node (ref "C_IC3") (pin "1") (pinfunction "1_1") (pintype "passive"))
      (node (ref "C_IC4") (pin "1") (pinfunction "1_1") (pintype "passive"))
      (node (ref "C_IC5") (pin "1") (pinfunction "1_1") (pintype "passive"))
      (node (ref "C_IC6") (pin "1") (pinfunction "1_1") (pintype "passive"))
      (node (ref "C_IC7") (pin "1") (pinfunction "1_1") (pintype "passive"))
      (node (ref "C_IC8") (pin "1") (pinfunction "1_1") (pintype "passive"))
      (node (ref "C_IC9") (pin "1") (pinfunction "1_1") (pintype "passive"))
      (node (ref "C_ICU8") (pin "1") (pinfunction "1_1") (pintype "passive"))
      (node (ref "DISSIP1") (pin "1") (pinfunction "A_1") (pintype "bidirectional"))
      (node (ref "DISSIP1") (pin "3") (pinfunction "NC_3") (pintype "bidirectional"))
      (node (ref "DISSIP2") (pin "1") (pinfunction "A_1") (pintype "bidirectional"))
      (node (ref "DISSIP2") (pin "3") (pinfunction "NC_3") (pintype "bidirectional"))
      (node (ref "IC10") (pin "4") (pinfunction "V-_4") (pintype "power_in"))
      (node (ref "IC11") (pin "4") (pinfunction "V-_4") (pintype "power_in"))
      (node (ref "IC12") (pin "4") (pinfunction "V-_4") (pintype "power_in"))
      (node (ref "IC2") (pin "4") (pinfunction "V-_4") (pintype "power_in"))
      (node (ref "IC3") (pin "4") (pinfunction "V-_4") (pintype "power_in"))
      (node (ref "IC4") (pin "4") (pinfunction "V-_4") (pintype "power_in"))
      (node (ref "IC5") (pin "4") (pinfunction "V-_4") (pintype "power_in"))
      (node (ref "IC6") (pin "4") (pinfunction "V-_4") (pintype "power_in"))
      (node (ref "IC7") (pin "4") (pinfunction "V-_4") (pintype "power_in"))
      (node (ref "IC8") (pin "4") (pinfunction "V-_4") (pintype "power_in"))
      (node (ref "IC8") (pin "5") (pinfunction "+IN_5") (pintype "input"))
      (node (ref "IC8") (pin "6") (pinfunction "-IN_6") (pintype "input"))
      (node (ref "IC9") (pin "4") (pinfunction "V-_4") (pintype "power_in"))
      (node (ref "IC9") (pin "5") (pinfunction "+IN_5") (pintype "input"))
      (node (ref "IC9") (pin "6") (pinfunction "-IN_6") (pintype "input"))
      (node (ref "LTC3411") (pin "3") (pinfunction "SGND_3") (pintype "bidirectional"))
      (node (ref "LTC3411") (pin "5") (pinfunction "PGND_5") (pintype "bidirectional"))
      (node (ref "PW_EXT1") (pin "1") (pinfunction "1_1") (pintype "passive"))
      (node (ref "PW_EXT1") (pin "2") (pinfunction "2_2") (pintype "passive"))
      (node (ref "PW_EXT2") (pin "1") (pinfunction "1_1") (pintype "passive"))
      (node (ref "PW_EXT2") (pin "2") (pinfunction "2_2") (pintype "passive"))
      (node (ref "PW_EXT3") (pin "1") (pinfunction "1_1") (pintype "passive"))
      (node (ref "PW_EXT3") (pin "2") (pinfunction "2_2") (pintype "passive"))
      (node (ref "R15") (pin "1") (pinfunction "1_1") (pintype "passive"))
      (node (ref "R17") (pin "2") (pinfunction "2_2") (pintype "passive"))
      (node (ref "R2") (pin "1") (pinfunction "1_1") (pintype "passive"))
      (node (ref "R20") (pin "1") (pinfunction "1_1") (pintype "passive"))
      (node (ref "R26") (pin "2") (pinfunction "2_2") (pintype "passive"))
      (node (ref "R34") (pin "2") (pinfunction "2_2") (pintype "passive"))
      (node (ref "R37") (pin "2") (pinfunction "2_2") (pintype "passive"))
      (node (ref "R42") (pin "2") (pinfunction "2_2") (pintype "passive"))
      (node (ref "R44") (pin "2") (pinfunction "2_2") (pintype "passive"))
      (node (ref "R48") (pin "1") (pinfunction "1_1") (pintype "passive"))
      (node (ref "R56") (pin "2") (pinfunction "2_2") (pintype "passive"))
      (node (ref "R59") (pin "2") (pinfunction "2_2") (pintype "passive"))
      (node (ref "R64") (pin "2") (pinfunction "2_2") (pintype "passive"))
      (node (ref "R67") (pin "2") (pinfunction "2_2") (pintype "passive"))
      (node (ref "R69") (pin "2") (pinfunction "2_2") (pintype "passive"))
      (node (ref "R73") (pin "2") (pinfunction "2_2") (pintype "passive"))
      (node (ref "R75") (pin "2") (pinfunction "2_2") (pintype "passive"))
      (node (ref "R77") (pin "2") (pinfunction "2_2") (pintype "passive"))
      (node (ref "SC_JMPR") (pin "1") (pinfunction "1_1") (pintype "passive"))
      (node (ref "SC_JMPR") (pin "3") (pinfunction "3_3") (pintype "passive"))
      (node (ref "U$1") (pin "19") (pinfunction "19_19") (pintype "power_in"))
      (node (ref "U$1") (pin "49") (pinfunction "49_49") (pintype "power_in"))
      (node (ref "U$1") (pin "61") (pinfunction "61_61") (pintype "power_in"))
      (node (ref "U$1") (pin "68") (pinfunction "68_68") (pintype "power_in"))
      (node (ref "U$11") (pin "10") (pinfunction "GND_10") (pintype "bidirectional"))
      (node (ref "U$11") (pin "11") (pinfunction "PGND1_11") (pintype "bidirectional"))
      (node (ref "U$11") (pin "12") (pinfunction "PGND2_12") (pintype "bidirectional"))
      (node (ref "U$11") (pin "13") (pinfunction "PGND3_13") (pintype "bidirectional"))
      (node (ref "U$11") (pin "23") (pinfunction "LB1_23") (pintype "bidirectional"))
      (node (ref "U$11") (pin "4") (pinfunction "ENB_4") (pintype "bidirectional"))
      (node (ref "U$11") (pin "7") (pinfunction "SYNC_7") (pintype "bidirectional"))
      (node (ref "U$11") (pin "EXP") (pinfunction "EP_EXP") (pintype "bidirectional"))
      (node (ref "U$12") (pin "2") (pinfunction "S_2") (pintype "bidirectional"))
      (node (ref "U$13") (pin "2") (pinfunction "S_2") (pintype "bidirectional"))
      (node (ref "U$14") (pin "2") (pinfunction "S_2") (pintype "bidirectional"))
      (node (ref "U$15") (pin "2") (pinfunction "S_2") (pintype "bidirectional"))
      (node (ref "U$16") (pin "1") (pinfunction "GND_1") (pintype "bidirectional"))
      (node (ref "U$17") (pin "1") (pinfunction "GND_1") (pintype "bidirectional"))
      (node (ref "U$18") (pin "1") (pinfunction "GND_1") (pintype "bidirectional"))
      (node (ref "U$19") (pin "2") (pinfunction "GND_2") (pintype "bidirectional"))
      (node (ref "U$2") (pin "3") (pinfunction "GND_3") (pintype "bidirectional"))
      (node (ref "U$20") (pin "2") (pinfunction "GND_2") (pintype "bidirectional"))
      (node (ref "U$3") (pin "3") (pinfunction "GND_3") (pintype "bidirectional"))
      (node (ref "U$4") (pin "3") (pinfunction "GND_3") (pintype "bidirectional"))
      (node (ref "U$5") (pin "3") (pinfunction "GND_3") (pintype "bidirectional"))
      (node (ref "U$8") (pin "2") (pinfunction "V-_2") (pintype "bidirectional"))
      (node (ref "U$9") (pin "2") (pinfunction "S_2") (pintype "bidirectional"))
    )
    (net (code "36") (name "Net-(C1-Pad1)") (class "Default")
      (node (ref "C1") (pin "1") (pinfunction "1_1") (pintype "passive"))
      (node (ref "R4") (pin "1") (pinfunction "1_1") (pintype "passive"))
    )
    (net (code "37") (name "Net-(C8-Pad2)") (class "Default")
      (node (ref "C8") (pin "2") (pinfunction "2_2") (pintype "passive"))
      (node (ref "R32") (pin "1") (pinfunction "1_1") (pintype "passive"))
    )
    (net (code "38") (name "Net-(C13-Pad2)") (class "Default")
      (node (ref "C13") (pin "2") (pinfunction "2_2") (pintype "passive"))
      (node (ref "R38") (pin "2") (pinfunction "2_2") (pintype "passive"))
    )
    (net (code "39") (name "Net-(C14-Pad1)") (class "Default")
      (node (ref "C14") (pin "1") (pinfunction "1_1") (pintype "passive"))
      (node (ref "Q1") (pin "2") (pinfunction "2_2") (pintype "passive"))
      (node (ref "U$1") (pin "12") (pinfunction "12_12") (pintype "bidirectional"))
    )
    (net (code "40") (name "Net-(C15-Pad1)") (class "Default")
      (node (ref "C15") (pin "1") (pinfunction "1_1") (pintype "passive"))
      (node (ref "Q1") (pin "1") (pinfunction "1_1") (pintype "passive"))
      (node (ref "U$1") (pin "13") (pinfunction "13_13") (pintype "bidirectional"))
    )
    (net (code "41") (name "Net-(C16-Pad2)") (class "Default")
      (node (ref "C16") (pin "2") (pinfunction "2_2") (pintype "passive"))
      (node (ref "R52") (pin "1") (pinfunction "1_1") (pintype "passive"))
    )
    (net (code "42") (name "Net-(C17-Pad+)") (class "Default")
      (node (ref "C17") (pin "+") (pinfunction "+_+") (pintype "passive"))
      (node (ref "L2") (pin "2") (pinfunction "2_2") (pintype "passive"))
      (node (ref "R55") (pin "1") (pinfunction "1_1") (pintype "passive"))
      (node (ref "R57") (pin "2") (pinfunction "2_2") (pintype "passive"))
      (node (ref "R71") (pin "1") (pinfunction "1_1") (pintype "passive"))
    )
    (net (code "43") (name "Net-(C18-Pad2)") (class "Default")
      (node (ref "C18") (pin "2") (pinfunction "2_2") (pintype "passive"))
      (node (ref "R60") (pin "2") (pinfunction "2_2") (pintype "passive"))
    )
    (net (code "44") (name "Net-(C20-Pad1)") (class "Default")
      (node (ref "C20") (pin "1") (pinfunction "1_1") (pintype "passive"))
      (node (ref "U$1") (pin "20") (pinfunction "20_20") (pintype "power_in"))
    )
    (net (code "45") (name "Net-(C25-Pad2)") (class "Default")
      (node (ref "C25") (pin "2") (pinfunction "2_2") (pintype "passive"))
      (node (ref "R74") (pin "2") (pinfunction "2_2") (pintype "passive"))
    )
    (net (code "46") (name "Net-(DISSIP1-B)") (class "Default")
      (node (ref "DISSIP1") (pin "2") (pinfunction "B_2") (pintype "bidirectional"))
      (node (ref "IC8") (pin "2") (pinfunction "-IN_2") (pintype "input"))
      (node (ref "U$6") (pin "3") (pinfunction "E_3") (pintype "passive"))
    )
    (net (code "47") (name "Net-(DISSIP2-B)") (class "Default")
      (node (ref "DISSIP2") (pin "2") (pinfunction "B_2") (pintype "bidirectional"))
      (node (ref "IC9") (pin "2") (pinfunction "-IN_2") (pintype "input"))
      (node (ref "U$7") (pin "3") (pinfunction "E_3") (pintype "passive"))
    )
    (net (code "48") (name "Net-(IC2A--IN)") (class "Default")
      (node (ref "IC2") (pin "2") (pinfunction "-IN_2") (pintype "input"))
      (node (ref "R1") (pin "1") (pinfunction "1_1") (pintype "passive"))
      (node (ref "R2") (pin "2") (pinfunction "2_2") (pintype "passive"))
      (node (ref "R3") (pin "2") (pinfunction "2_2") (pintype "passive"))
    )
    (net (code "49") (name "Net-(IC2A-OUT)") (class "Default")
      (node (ref "IC2") (pin "1") (pinfunction "OUT_1") (pintype "output"))
      (node (ref "R3") (pin "1") (pinfunction "1_1") (pintype "passive"))
      (node (ref "R5") (pin "2") (pinfunction "2_2") (pintype "passive"))
    )
    (net (code "50") (name "Net-(IC2B--IN)") (class "Default")
      (node (ref "IC2") (pin "6") (pinfunction "-IN_6") (pintype "input"))
      (node (ref "R4") (pin "2") (pinfunction "2_2") (pintype "passive"))
      (node (ref "R5") (pin "1") (pinfunction "1_1") (pintype "passive"))
    )
    (net (code "51") (name "Net-(IC3A-+IN)") (class "Default")
      (node (ref "C2") (pin "2") (pinfunction "2_2") (pintype "passive"))
      (node (ref "IC3") (pin "3") (pinfunction "+IN_3") (pintype "input"))
      (node (ref "R7") (pin "1") (pinfunction "1_1") (pintype "passive"))
    )
    (net (code "52") (name "Net-(IC3B-+IN)") (class "Default")
      (node (ref "C3") (pin "2") (pinfunction "2_2") (pintype "passive"))
      (node (ref "IC3") (pin "5") (pinfunction "+IN_5") (pintype "input"))
      (node (ref "R9") (pin "1") (pinfunction "1_1") (pintype "passive"))
    )
    (net (code "53") (name "Net-(IC4A-+IN)") (class "Default")
      (node (ref "C4") (pin "2") (pinfunction "2_2") (pintype "passive"))
      (node (ref "IC4") (pin "3") (pinfunction "+IN_3") (pintype "input"))
      (node (ref "R11") (pin "1") (pinfunction "1_1") (pintype "passive"))
    )
    (net (code "54") (name "Net-(IC4B-+IN)") (class "Default")
      (node (ref "C5") (pin "2") (pinfunction "2_2") (pintype "passive"))
      (node (ref "IC4") (pin "5") (pinfunction "+IN_5") (pintype "input"))
      (node (ref "R13") (pin "1") (pinfunction "1_1") (pintype "passive"))
    )
    (net (code "55") (name "Net-(IC5A-+IN)") (class "Default")
      (node (ref "IC5") (pin "3") (pinfunction "+IN_3") (pintype "input"))
      (node (ref "R14") (pin "1") (pinfunction "1_1") (pintype "passive"))
      (node (ref "R15") (pin "2") (pinfunction "2_2") (pintype "passive"))
    )
    (net (code "56") (name "Net-(IC5A--IN)") (class "Default")
      (node (ref "IC5") (pin "2") (pinfunction "-IN_2") (pintype "input"))
      (node (ref "R17") (pin "1") (pinfunction "1_1") (pintype "passive"))
      (node (ref "R18") (pin "2") (pinfunction "2_2") (pintype "passive"))
    )
    (net (code "57") (name "Net-(IC5A-OUT)") (class "Default")
      (node (ref "IC5") (pin "1") (pinfunction "OUT_1") (pintype "output"))
      (node (ref "R16") (pin "2") (pinfunction "2_2") (pintype "passive"))
      (node (ref "R18") (pin "1") (pinfunction "1_1") (pintype "passive"))
    )
    (net (code "58") (name "Net-(IC5B-+IN)") (class "Default")
      (node (ref "C6") (pin "2") (pinfunction "2_2") (pintype "passive"))
      (node (ref "IC5") (pin "5") (pinfunction "+IN_5") (pintype "input"))
      (node (ref "R16") (pin "1") (pinfunction "1_1") (pintype "passive"))
    )
    (net (code "59") (name "Net-(IC6A-+IN)") (class "Default")
      (node (ref "IC6") (pin "3") (pinfunction "+IN_3") (pintype "input"))
      (node (ref "R19") (pin "1") (pinfunction "1_1") (pintype "passive"))
      (node (ref "R20") (pin "2") (pinfunction "2_2") (pintype "passive"))
    )
    (net (code "60") (name "Net-(IC6A--IN)") (class "Default")
      (node (ref "IC6") (pin "2") (pinfunction "-IN_2") (pintype "input"))
      (node (ref "R22") (pin "1") (pinfunction "1_1") (pintype "passive"))
      (node (ref "R23") (pin "2") (pinfunction "2_2") (pintype "passive"))
    )
    (net (code "61") (name "Net-(IC6A-OUT)") (class "Default")
      (node (ref "IC6") (pin "1") (pinfunction "OUT_1") (pintype "output"))
      (node (ref "R21") (pin "2") (pinfunction "2_2") (pintype "passive"))
      (node (ref "R23") (pin "1") (pinfunction "1_1") (pintype "passive"))
    )
    (net (code "62") (name "Net-(IC6B-+IN)") (class "Default")
      (node (ref "C7") (pin "2") (pinfunction "2_2") (pintype "passive"))
      (node (ref "IC6") (pin "5") (pinfunction "+IN_5") (pintype "input"))
      (node (ref "R21") (pin "1") (pinfunction "1_1") (pintype "passive"))
    )
    (net (code "63") (name "Net-(IC7A-+IN)") (class "Default")
      (node (ref "IC7") (pin "3") (pinfunction "+IN_3") (pintype "input"))
      (node (ref "R24") (pin "2") (pinfunction "2_2") (pintype "passive"))
      (node (ref "R25") (pin "1") (pinfunction "1_1") (pintype "passive"))
    )
    (net (code "64") (name "Net-(IC7A--IN)") (class "Default")
      (node (ref "IC7") (pin "1") (pinfunction "OUT_1") (pintype "output"))
      (node (ref "IC7") (pin "2") (pinfunction "-IN_2") (pintype "input"))
    )
    (net (code "65") (name "Net-(IC7B-+IN)") (class "Default")
      (node (ref "IC7") (pin "5") (pinfunction "+IN_5") (pintype "input"))
      (node (ref "R25") (pin "2") (pinfunction "2_2") (pintype "passive"))
      (node (ref "R26") (pin "1") (pinfunction "1_1") (pintype "passive"))
    )
    (net (code "66") (name "Net-(IC7B--IN)") (class "Default")
      (node (ref "IC7") (pin "6") (pinfunction "-IN_6") (pintype "input"))
      (node (ref "R27") (pin "1") (pinfunction "1_1") (pintype "passive"))
      (node (ref "R28") (pin "2") (pinfunction "2_2") (pintype "passive"))
    )
    (net (code "67") (name "Net-(IC7B-OUT)") (class "Default")
      (node (ref "IC7") (pin "7") (pinfunction "OUT_7") (pintype "output"))
      (node (ref "R28") (pin "1") (pinfunction "1_1") (pintype "passive"))
      (node (ref "R29") (pin "2") (pinfunction "2_2") (pintype "passive"))
    )
    (net (code "68") (name "Net-(IC8A-+IN)") (class "Default")
      (node (ref "IC8") (pin "3") (pinfunction "+IN_3") (pintype "input"))
      (node (ref "IC9") (pin "3") (pinfunction "+IN_3") (pintype "input"))
      (node (ref "R29") (pin "1") (pinfunction "1_1") (pintype "passive"))
    )
    (net (code "69") (name "Net-(IC8A-OUT)") (class "Default")
      (node (ref "IC8") (pin "1") (pinfunction "OUT_1") (pintype "output"))
      (node (ref "U$6") (pin "1") (pinfunction "B_1") (pintype "passive"))
    )
    (net (code "70") (name "Net-(IC9A-OUT)") (class "Default")
      (node (ref "IC9") (pin "1") (pinfunction "OUT_1") (pintype "output"))
      (node (ref "U$7") (pin "1") (pinfunction "B_1") (pintype "passive"))
    )
    (net (code "71") (name "Net-(IC10A--IN)") (class "Default")
      (node (ref "IC10") (pin "2") (pinfunction "-IN_2") (pintype "input"))
      (node (ref "R30") (pin "1") (pinfunction "1_1") (pintype "passive"))
      (node (ref "R31") (pin "1") (pinfunction "1_1") (pintype "passive"))
      (node (ref "R32") (pin "2") (pinfunction "2_2") (pintype "passive"))
    )
    (net (code "72") (name "Net-(IC10A-OUT)") (class "Default")
      (node (ref "C8") (pin "1") (pinfunction "1_1") (pintype "passive"))
      (node (ref "IC10") (pin "1") (pinfunction "OUT_1") (pintype "output"))
      (node (ref "R33") (pin "2") (pinfunction "2_2") (pintype "passive"))
    )
    (net (code "73") (name "Net-(IC10B-+IN)") (class "Default")
      (node (ref "IC10") (pin "5") (pinfunction "+IN_5") (pintype "input"))
      (node (ref "R40") (pin "2") (pinfunction "2_2") (pintype "passive"))
      (node (ref "R45") (pin "2") (pinfunction "2_2") (pintype "passive"))
    )
    (net (code "74") (name "Net-(IC10B--IN)") (class "Default")
      (node (ref "IC10") (pin "6") (pinfunction "-IN_6") (pintype "input"))
      (node (ref "R41") (pin "2") (pinfunction "2_2") (pintype "passive"))
      (node (ref "R43") (pin "1") (pinfunction "1_1") (pintype "passive"))
    )
    (net (code "75") (name "Net-(IC10B-OUT)") (class "Default")
      (node (ref "IC10") (pin "7") (pinfunction "OUT_7") (pintype "output"))
      (node (ref "R30") (pin "2") (pinfunction "2_2") (pintype "passive"))
      (node (ref "R43") (pin "2") (pinfunction "2_2") (pintype "passive"))
    )
    (net (code "76") (name "Net-(IC11A--IN)") (class "Default")
      (node (ref "IC11") (pin "2") (pinfunction "-IN_2") (pintype "input"))
      (node (ref "R49") (pin "1") (pinfunction "1_1") (pintype "passive"))
      (node (ref "R50") (pin "2") (pinfunction "2_2") (pintype "passive"))
    )
    (net (code "77") (name "Net-(IC11A-OUT)") (class "Default")
      (node (ref "IC11") (pin "1") (pinfunction "OUT_1") (pintype "output"))
      (node (ref "R50") (pin "1") (pinfunction "1_1") (pintype "passive"))
      (node (ref "R51") (pin "2") (pinfunction "2_2") (pintype "passive"))
    )
    (net (code "78") (name "Net-(IC11B--IN)") (class "Default")
      (node (ref "IC11") (pin "6") (pinfunction "-IN_6") (pintype "input"))
      (node (ref "R51") (pin "1") (pinfunction "1_1") (pintype "passive"))
      (node (ref "R52") (pin "2") (pinfunction "2_2") (pintype "passive"))
      (node (ref "R53") (pin "2") (pinfunction "2_2") (pintype "passive"))
    )
    (net (code "79") (name "Net-(IC11B-OUT)") (class "Default")
      (node (ref "C16") (pin "1") (pinfunction "1_1") (pintype "passive"))
      (node (ref "IC11") (pin "7") (pinfunction "OUT_7") (pintype "output"))
      (node (ref "R54") (pin "2") (pinfunction "2_2") (pintype "passive"))
    )
    (net (code "80") (name "Net-(IC12A-+IN)") (class "Default")
      (node (ref "IC12") (pin "3") (pinfunction "+IN_3") (pintype "input"))
      (node (ref "R62") (pin "2") (pinfunction "2_2") (pintype "passive"))
      (node (ref "R63") (pin "2") (pinfunction "2_2") (pintype "passive"))
    )
    (net (code "81") (name "Net-(IC12A--IN)") (class "Default")
      (node (ref "IC12") (pin "2") (pinfunction "-IN_2") (pintype "input"))
      (node (ref "R58") (pin "1") (pinfunction "1_1") (pintype "passive"))
      (node (ref "R71") (pin "2") (pinfunction "2_2") (pintype "passive"))
    )
    (net (code "82") (name "Net-(IC12A-OUT)") (class "Default")
      (node (ref "IC12") (pin "1") (pinfunction "OUT_1") (pintype "output"))
      (node (ref "R53") (pin "1") (pinfunction "1_1") (pintype "passive"))
      (node (ref "R58") (pin "2") (pinfunction "2_2") (pintype "passive"))
    )
    (net (code "83") (name "Net-(LTC3411-ITH)") (class "Default")
      (node (ref "LTC3411") (pin "10") (pinfunction "ITH_10") (pintype "bidirectional"))
      (node (ref "R60") (pin "1") (pinfunction "1_1") (pintype "passive"))
    )
    (net (code "84") (name "Net-(LTC3411-PGOOD)") (class "Default")
      (node (ref "LTC3411") (pin "8") (pinfunction "PGOOD_8") (pintype "bidirectional"))
      (node (ref "R65") (pin "2") (pinfunction "2_2") (pintype "passive"))
    )
    (net (code "85") (name "Net-(LTC3411-PVIN)") (class "Default")
      (node (ref "LTC3411") (pin "6") (pinfunction "PVIN_6") (pintype "bidirectional"))
      (node (ref "LTC3411") (pin "7") (pinfunction "SVIN_7") (pintype "bidirectional"))
      (node (ref "R65") (pin "1") (pinfunction "1_1") (pintype "passive"))
    )
    (net (code "86") (name "Net-(LTC3411-SHDN{slash}RT)") (class "Default")
      (node (ref "LTC3411") (pin "1") (pinfunction "SHDN/RT_1") (pintype "bidirectional"))
      (node (ref "R59") (pin "1") (pinfunction "1_1") (pintype "passive"))
      (node (ref "U$10") (pin "3") (pinfunction "D_3") (pintype "bidirectional"))
    )
    (net (code "87") (name "Net-(LTC3411-SW)") (class "Default")
      (node (ref "L2") (pin "1") (pinfunction "1_1") (pintype "passive"))
      (node (ref "LTC3411") (pin "4") (pinfunction "SW_4") (pintype "bidirectional"))
    )
    (net (code "88") (name "Net-(LTC3411-SYNC{slash}MODE)") (class "Default")
      (node (ref "LTC3411") (pin "2") (pinfunction "SYNC/MODE_2") (pintype "bidirectional"))
      (node (ref "R61") (pin "2") (pinfunction "2_2") (pintype "passive"))
      (node (ref "R64") (pin "1") (pinfunction "1_1") (pintype "passive"))
    )
    (net (code "89") (name "Net-(LTC3411-VFB)") (class "Default")
      (node (ref "LTC3411") (pin "9") (pinfunction "VFB_9") (pintype "bidirectional"))
      (node (ref "R54") (pin "1") (pinfunction "1_1") (pintype "passive"))
      (node (ref "R55") (pin "2") (pinfunction "2_2") (pintype "passive"))
      (node (ref "R56") (pin "1") (pinfunction "1_1") (pintype "passive"))
    )
    (net (code "90") (name "Net-(R48-Pad2)") (class "Default")
      (node (ref "R48") (pin "2") (pinfunction "2_2") (pintype "passive"))
      (node (ref "U$1") (pin "63") (pinfunction "63_63") (pintype "bidirectional"))
    )
    (net (code "91") (name "Net-(U$2-OUT)") (class "Default")
      (node (ref "R9") (pin "2") (pinfunction "2_2") (pintype "passive"))
      (node (ref "U$2") (pin "4") (pinfunction "OUT_4") (pintype "bidirectional"))
    )
    (net (code "92") (name "Net-(U$3-OUT)") (class "Default")
      (node (ref "R7") (pin "2") (pinfunction "2_2") (pintype "passive"))
      (node (ref "U$3") (pin "4") (pinfunction "OUT_4") (pintype "bidirectional"))
    )
    (net (code "93") (name "Net-(U$4-OUT)") (class "Default")
      (node (ref "R11") (pin "2") (pinfunction "2_2") (pintype "passive"))
      (node (ref "U$4") (pin "4") (pinfunction "OUT_4") (pintype "bidirectional"))
    )
    (net (code "94") (name "Net-(U$5-OUT)") (class "Default")
      (node (ref "R13") (pin "2") (pinfunction "2_2") (pintype "passive"))
      (node (ref "U$5") (pin "4") (pinfunction "OUT_4") (pintype "bidirectional"))
    )
    (net (code "95") (name "Net-(U$8-HYST)") (class "Default")
      (node (ref "R75") (pin "1") (pinfunction "1_1") (pintype "passive"))
      (node (ref "R76") (pin "2") (pinfunction "2_2") (pintype "passive"))
      (node (ref "U$8") (pin "5") (pinfunction "HYST_5") (pintype "bidirectional"))
    )
    (net (code "96") (name "Net-(U$8-INA+)") (class "Default")
      (node (ref "R72") (pin "2") (pinfunction "2_2") (pintype "passive"))
      (node (ref "R73") (pin "1") (pinfunction "1_1") (pintype "passive"))
      (node (ref "U$8") (pin "3") (pinfunction "INA+_3") (pintype "bidirectional"))
    )
    (net (code "97") (name "Net-(U$8-INB-)") (class "Default")
      (node (ref "R66") (pin "2") (pinfunction "2_2") (pintype "passive"))
      (node (ref "R67") (pin "1") (pinfunction "1_1") (pintype "passive"))
      (node (ref "U$8") (pin "4") (pinfunction "INB-_4") (pintype "bidirectional"))
    )
    (net (code "98") (name "Net-(U$8-OUTB)") (class "Default")
      (node (ref "R68") (pin "2") (pinfunction "2_2") (pintype "passive"))
      (node (ref "U$8") (pin "8") (pinfunction "OUTB_8") (pintype "bidirectional"))
    )
    (net (code "99") (name "Net-(U$8-REF)") (class "Default")
      (node (ref "R74") (pin "1") (pinfunction "1_1") (pintype "passive"))
      (node (ref "R76") (pin "1") (pinfunction "1_1") (pintype "passive"))
      (node (ref "U$8") (pin "6") (pinfunction "REF_6") (pintype "bidirectional"))
    )
    (net (code "100") (name "Net-(U$9-G)") (class "Default")
      (node (ref "R68") (pin "1") (pinfunction "1_1") (pintype "passive"))
      (node (ref "R69") (pin "1") (pinfunction "1_1") (pintype "passive"))
      (node (ref "U$9") (pin "1") (pinfunction "G_1") (pintype "bidirectional"))
    )
    (net (code "101") (name "Net-(U$10-G)") (class "Default")
      (node (ref "R70") (pin "2") (pinfunction "2_2") (pintype "passive"))
      (node (ref "U$10") (pin "1") (pinfunction "G_1") (pintype "bidirectional"))
      (node (ref "U$9") (pin "3") (pinfunction "D_3") (pintype "bidirectional"))
    )
    (net (code "102") (name "Net-(U$11-BURST)") (class "Default")
      (node (ref "C10") (pin "2") (pinfunction "2_2") (pintype "passive"))
      (node (ref "R36") (pin "2") (pinfunction "2_2") (pintype "passive"))
      (node (ref "R44") (pin "1") (pinfunction "1_1") (pintype "passive"))
      (node (ref "U$11") (pin "9") (pinfunction "BURST_9") (pintype "bidirectional"))
    )
    (net (code "103") (name "Net-(U$11-FB)") (class "Default")
      (node (ref "R33") (pin "1") (pinfunction "1_1") (pintype "passive"))
      (node (ref "R34") (pin "1") (pinfunction "1_1") (pintype "passive"))
      (node (ref "R35") (pin "2") (pinfunction "2_2") (pintype "passive"))
      (node (ref "U$11") (pin "1") (pinfunction "FB_1") (pintype "bidirectional"))
    )
    (net (code "104") (name "Net-(U$11-ILIM)") (class "Default")
      (node (ref "R42") (pin "1") (pinfunction "1_1") (pintype "passive"))
      (node (ref "U$11") (pin "8") (pinfunction "ILIM_8") (pintype "bidirectional"))
    )
    (net (code "105") (name "Net-(U$11-RT)") (class "Default")
      (node (ref "R37") (pin "1") (pinfunction "1_1") (pintype "passive"))
      (node (ref "U$11") (pin "5") (pinfunction "RT_5") (pintype "bidirectional"))
    )
    (net (code "106") (name "Net-(U$11-SHDN)") (class "Default")
      (node (ref "U$11") (pin "2") (pinfunction "SHDN_2") (pintype "bidirectional"))
      (node (ref "U$12") (pin "3") (pinfunction "D_3") (pintype "bidirectional"))
    )
    (net (code "107") (name "Net-(U$11-SS)") (class "Default")
      (node (ref "C11") (pin "2") (pinfunction "2_2") (pintype "passive"))
      (node (ref "U$11") (pin "6") (pinfunction "SS_6") (pintype "bidirectional"))
    )
    (net (code "108") (name "Net-(U$11-SW1)") (class "Default")
      (node (ref "L1") (pin "2") (pinfunction "2_2") (pintype "passive"))
      (node (ref "U$11") (pin "14") (pinfunction "SW1_14") (pintype "bidirectional"))
      (node (ref "U$11") (pin "15") (pinfunction "SW2_15") (pintype "bidirectional"))
      (node (ref "U$11") (pin "16") (pinfunction "SW3_16") (pintype "bidirectional"))
    )
    (net (code "109") (name "Net-(U$11-VC)") (class "Default")
      (node (ref "R38") (pin "1") (pinfunction "1_1") (pintype "passive"))
      (node (ref "U$11") (pin "24") (pinfunction "VC_24") (pintype "bidirectional"))
    )
    (net (code "110") (name "Net-(U$11-VOUT1)") (class "Default")
      (node (ref "C9") (pin "+") (pinfunction "+_+") (pintype "passive"))
      (node (ref "R35") (pin "1") (pinfunction "1_1") (pintype "passive"))
      (node (ref "R36") (pin "1") (pinfunction "1_1") (pintype "passive"))
      (node (ref "R39") (pin "2") (pinfunction "2_2") (pintype "passive"))
      (node (ref "R41") (pin "1") (pinfunction "1_1") (pintype "passive"))
      (node (ref "U$11") (pin "17") (pinfunction "VOUT1_17") (pintype "bidirectional"))
      (node (ref "U$11") (pin "18") (pinfunction "VOUTS_18") (pintype "bidirectional"))
      (node (ref "U$11") (pin "19") (pinfunction "VOUT2_19") (pintype "bidirectional"))
      (node (ref "U$11") (pin "20") (pinfunction "VOUT3_20") (pintype "bidirectional"))
    )
    (net (code "111") (name "Net-(U$12-G)") (class "Default")
      (node (ref "R77") (pin "1") (pinfunction "1_1") (pintype "passive"))
      (node (ref "R78") (pin "2") (pinfunction "2_2") (pintype "passive"))
      (node (ref "U$12") (pin "1") (pinfunction "G_1") (pintype "bidirectional"))
    )
    (net (code "112") (name "Net-(U$13-D)") (class "Default")
      (node (ref "R81") (pin "2") (pinfunction "2_2") (pintype "passive"))
      (node (ref "U$13") (pin "3") (pinfunction "D_3") (pintype "bidirectional"))
      (node (ref "U$16") (pin "4") (pinfunction "EN_4") (pintype "bidirectional"))
    )
    (net (code "113") (name "Net-(U$14-D)") (class "Default")
      (node (ref "R79") (pin "2") (pinfunction "2_2") (pintype "passive"))
      (node (ref "U$14") (pin "3") (pinfunction "D_3") (pintype "bidirectional"))
      (node (ref "U$18") (pin "4") (pinfunction "EN_4") (pintype "bidirectional"))
    )
    (net (code "114") (name "Net-(U$15-D)") (class "Default")
      (node (ref "R80") (pin "2") (pinfunction "2_2") (pintype "passive"))
      (node (ref "U$15") (pin "3") (pinfunction "D_3") (pintype "bidirectional"))
      (node (ref "U$17") (pin "4") (pinfunction "EN_4") (pintype "bidirectional"))
    )
    (net (code "115") (name "VCC") (class "Default")
      (node (ref "C12") (pin "+") (pinfunction "+_+") (pintype "passive"))
      (node (ref "C21") (pin "1") (pinfunction "1_1") (pintype "passive"))
      (node (ref "C27") (pin "2") (pinfunction "2_2") (pintype "passive"))
      (node (ref "C30") (pin "2") (pinfunction "2_2") (pintype "passive"))
      (node (ref "C_IC10") (pin "2") (pinfunction "2_2") (pintype "passive"))
      (node (ref "C_IC11") (pin "2") (pinfunction "2_2") (pintype "passive"))
      (node (ref "C_IC12") (pin "2") (pinfunction "2_2") (pintype "passive"))
      (node (ref "C_IC2") (pin "2") (pinfunction "2_2") (pintype "passive"))
      (node (ref "C_IC3") (pin "2") (pinfunction "2_2") (pintype "passive"))
      (node (ref "C_IC4") (pin "2") (pinfunction "2_2") (pintype "passive"))
      (node (ref "C_IC5") (pin "2") (pinfunction "2_2") (pintype "passive"))
      (node (ref "C_IC6") (pin "2") (pinfunction "2_2") (pintype "passive"))
      (node (ref "C_IC7") (pin "2") (pinfunction "2_2") (pintype "passive"))
      (node (ref "C_IC8") (pin "2") (pinfunction "2_2") (pintype "passive"))
      (node (ref "C_IC9") (pin "2") (pinfunction "2_2") (pintype "passive"))
      (node (ref "C_ICU8") (pin "2") (pinfunction "2_2") (pintype "passive"))
      (node (ref "FERRITE_BEAD") (pin "1") (pinfunction "1_1") (pintype "passive"))
      (node (ref "IC10") (pin "8") (pinfunction "V+_8") (pintype "power_in"))
      (node (ref "IC11") (pin "8") (pinfunction "V+_8") (pintype "power_in"))
      (node (ref "IC12") (pin "8") (pinfunction "V+_8") (pintype "power_in"))
      (node (ref "IC2") (pin "8") (pinfunction "V+_8") (pintype "power_in"))
      (node (ref "IC3") (pin "8") (pinfunction "V+_8") (pintype "power_in"))
      (node (ref "IC4") (pin "8") (pinfunction "V+_8") (pintype "power_in"))
      (node (ref "IC5") (pin "8") (pinfunction "V+_8") (pintype "power_in"))
      (node (ref "IC6") (pin "8") (pinfunction "V+_8") (pintype "power_in"))
      (node (ref "IC7") (pin "8") (pinfunction "V+_8") (pintype "power_in"))
      (node (ref "IC8") (pin "8") (pinfunction "V+_8") (pintype "power_in"))
      (node (ref "IC9") (pin "8") (pinfunction "V+_8") (pintype "power_in"))
      (node (ref "L1") (pin "1") (pinfunction "1_1") (pintype "passive"))
      (node (ref "R1") (pin "2") (pinfunction "2_2") (pintype "passive"))
      (node (ref "R14") (pin "2") (pinfunction "2_2") (pintype "passive"))
      (node (ref "R24") (pin "1") (pinfunction "1_1") (pintype "passive"))
      (node (ref "R57") (pin "1") (pinfunction "1_1") (pintype "passive"))
      (node (ref "R6") (pin "1") (pinfunction "1_1") (pintype "passive"))
      (node (ref "R63") (pin "1") (pinfunction "1_1") (pintype "passive"))
      (node (ref "R79") (pin "1") (pinfunction "1_1") (pintype "passive"))
      (node (ref "R8") (pin "2") (pinfunction "2_2") (pintype "passive"))
      (node (ref "R80") (pin "1") (pinfunction "1_1") (pintype "passive"))
      (node (ref "R81") (pin "1") (pinfunction "1_1") (pintype "passive"))
      (node (ref "U$1") (pin "11") (pinfunction "11_11") (pintype "power_in"))
      (node (ref "U$11") (pin "21") (pinfunction "VIN_21") (pintype "bidirectional"))
      (node (ref "U$19") (pin "3") (pinfunction "VIN_3") (pintype "bidirectional"))
      (node (ref "U$2") (pin "1") (pinfunction "VCC_1") (pintype "bidirectional"))
      (node (ref "U$2") (pin "6") (pinfunction "RS-_6") (pintype "bidirectional"))
      (node (ref "U$20") (pin "3") (pinfunction "VIN_3") (pintype "bidirectional"))
      (node (ref "U$3") (pin "1") (pinfunction "VCC_1") (pintype "bidirectional"))
      (node (ref "U$3") (pin "8") (pinfunction "RS+_8") (pintype "bidirectional"))
      (node (ref "U$4") (pin "1") (pinfunction "VCC_1") (pintype "bidirectional"))
      (node (ref "U$5") (pin "1") (pinfunction "VCC_1") (pintype "bidirectional"))
      (node (ref "U$6") (pin "2") (pinfunction "C_2") (pintype "passive"))
      (node (ref "U$7") (pin "2") (pinfunction "C_2") (pintype "passive"))
      (node (ref "U$8") (pin "7") (pinfunction "V+_7") (pintype "bidirectional"))
    )
    (net (code "116") (name "unconnected-(IC8B-OUT-Pad7)") (class "Default")
      (node (ref "IC8") (pin "7") (pinfunction "OUT_7") (pintype "output"))
    )
    (net (code "117") (name "unconnected-(IC9B-OUT-Pad7)") (class "Default")
      (node (ref "IC9") (pin "7") (pinfunction "OUT_7") (pintype "output"))
    )
    (net (code "118") (name "unconnected-(IC12B-+IN-Pad5)") (class "Default")
      (node (ref "IC12") (pin "5") (pinfunction "+IN_5") (pintype "input"))
    )
    (net (code "119") (name "unconnected-(IC12B--IN-Pad6)") (class "Default")
      (node (ref "IC12") (pin "6") (pinfunction "-IN_6") (pintype "input"))
    )
    (net (code "120") (name "unconnected-(IC12B-OUT-Pad7)") (class "Default")
      (node (ref "IC12") (pin "7") (pinfunction "OUT_7") (pintype "output"))
    )
    (net (code "121") (name "unconnected-(U$1-Pad7)") (class "Default")
      (node (ref "U$1") (pin "7") (pinfunction "7_7") (pintype "bidirectional"))
    )
    (net (code "122") (name "unconnected-(U$1-Pad8)") (class "Default")
      (node (ref "U$1") (pin "8") (pinfunction "8_8") (pintype "bidirectional"))
    )
    (net (code "123") (name "unconnected-(U$1-Pad9)") (class "Default")
      (node (ref "U$1") (pin "9") (pinfunction "9_9") (pintype "bidirectional"))
    )
    (net (code "124") (name "unconnected-(U$1-Pad10)") (class "Default")
      (node (ref "U$1") (pin "10") (pinfunction "10_10") (pintype "bidirectional"))
    )
    (net (code "125") (name "unconnected-(U$1-Pad15)") (class "Default")
      (node (ref "U$1") (pin "15") (pinfunction "15_15") (pintype "bidirectional"))
    )
    (net (code "126") (name "unconnected-(U$1-Pad16)") (class "Default")
      (node (ref "U$1") (pin "16") (pinfunction "16_16") (pintype "bidirectional"))
    )
    (net (code "127") (name "unconnected-(U$1-Pad17)") (class "Default")
      (node (ref "U$1") (pin "17") (pinfunction "17_17") (pintype "bidirectional"))
    )
    (net (code "128") (name "unconnected-(U$1-Pad21)") (class "Default")
      (node (ref "U$1") (pin "21") (pinfunction "21_21") (pintype "bidirectional"))
    )
    (net (code "129") (name "unconnected-(U$1-Pad22)") (class "Default")
      (node (ref "U$1") (pin "22") (pinfunction "22_22") (pintype "bidirectional"))
    )
    (net (code "130") (name "unconnected-(U$1-Pad23)") (class "Default")
      (node (ref "U$1") (pin "23") (pinfunction "23_23") (pintype "bidirectional"))
    )
    (net (code "131") (name "unconnected-(U$1-Pad24)") (class "Default")
      (node (ref "U$1") (pin "24") (pinfunction "24_24") (pintype "bidirectional"))
    )
    (net (code "132") (name "unconnected-(U$1-Pad25)") (class "Default")
      (node (ref "U$1") (pin "25") (pinfunction "25_25") (pintype "bidirectional"))
    )
    (net (code "133") (name "unconnected-(U$1-Pad26)") (class "Default")
      (node (ref "U$1") (pin "26") (pinfunction "26_26") (pintype "bidirectional"))
    )
    (net (code "134") (name "unconnected-(U$1-Pad27)") (class "Default")
      (node (ref "U$1") (pin "27") (pinfunction "27_27") (pintype "bidirectional"))
    )
    (net (code "135") (name "unconnected-(U$1-Pad28)") (class "Default")
      (node (ref "U$1") (pin "28") (pinfunction "28_28") (pintype "bidirectional"))
    )
    (net (code "136") (name "unconnected-(U$1-Pad29)") (class "Default")
      (node (ref "U$1") (pin "29") (pinfunction "29_29") (pintype "bidirectional"))
    )
    (net (code "137") (name "unconnected-(U$1-Pad30)") (class "Default")
      (node (ref "U$1") (pin "30") (pinfunction "30_30") (pintype "bidirectional"))
    )
    (net (code "138") (name "unconnected-(U$1-Pad31)") (class "Default")
      (node (ref "U$1") (pin "31") (pinfunction "31_31") (pintype "bidirectional"))
    )
    (net (code "139") (name "unconnected-(U$1-Pad32)") (class "Default")
      (node (ref "U$1") (pin "32") (pinfunction "32_32") (pintype "bidirectional"))
    )
    (net (code "140") (name "unconnected-(U$1-Pad33)") (class "Default")
      (node (ref "U$1") (pin "33") (pinfunction "33_33") (pintype "bidirectional"))
    )
    (net (code "141") (name "unconnected-(U$1-Pad34)") (class "Default")
      (node (ref "U$1") (pin "34") (pinfunction "34_34") (pintype "bidirectional"))
    )
    (net (code "142") (name "unconnected-(U$1-Pad35)") (class "Default")
      (node (ref "U$1") (pin "35") (pinfunction "35_35") (pintype "bidirectional"))
    )
    (net (code "143") (name "unconnected-(U$1-Pad36)") (class "Default")
      (node (ref "U$1") (pin "36") (pinfunction "36_36") (pintype "bidirectional"))
    )
    (net (code "144") (name "unconnected-(U$1-Pad37)") (class "Default")
      (node (ref "U$1") (pin "37") (pinfunction "37_37") (pintype "bidirectional"))
    )
    (net (code "145") (name "unconnected-(U$1-Pad38)") (class "Default")
      (node (ref "U$1") (pin "38") (pinfunction "38_38") (pintype "bidirectional"))
    )
    (net (code "146") (name "unconnected-(U$1-Pad39)") (class "Default")
      (node (ref "U$1") (pin "39") (pinfunction "39_39") (pintype "bidirectional"))
    )
    (net (code "147") (name "unconnected-(U$1-Pad40)") (class "Default")
      (node (ref "U$1") (pin "40") (pinfunction "40_40") (pintype "bidirectional"))
    )
    (net (code "148") (name "unconnected-(U$1-Pad41)") (class "Default")
      (node (ref "U$1") (pin "41") (pinfunction "41_41") (pintype "bidirectional"))
    )
    (net (code "149") (name "unconnected-(U$1-Pad42)") (class "Default")
      (node (ref "U$1") (pin "42") (pinfunction "42_42") (pintype "bidirectional"))
    )
    (net (code "150") (name "unconnected-(U$1-Pad43)") (class "Default")
      (node (ref "U$1") (pin "43") (pinfunction "43_43") (pintype "bidirectional"))
    )
    (net (code "151") (name "unconnected-(U$1-Pad44)") (class "Default")
      (node (ref "U$1") (pin "44") (pinfunction "44_44") (pintype "bidirectional"))
    )
    (net (code "152") (name "unconnected-(U$1-Pad48)") (class "Default")
      (node (ref "U$1") (pin "48") (pinfunction "48_48") (pintype "bidirectional"))
    )
    (net (code "153") (name "unconnected-(U$1-Pad51)") (class "Default")
      (node (ref "U$1") (pin "51") (pinfunction "51_51") (pintype "bidirectional"))
    )
    (net (code "154") (name "unconnected-(U$1-Pad52)") (class "Default")
      (node (ref "U$1") (pin "52") (pinfunction "52_52") (pintype "bidirectional"))
    )
    (net (code "155") (name "unconnected-(U$1-Pad53)") (class "Default")
      (node (ref "U$1") (pin "53") (pinfunction "53_53") (pintype "bidirectional"))
    )
    (net (code "156") (name "unconnected-(U$1-Pad54)") (class "Default")
      (node (ref "U$1") (pin "54") (pinfunction "54_54") (pintype "bidirectional"))
    )
    (net (code "157") (name "unconnected-(U$1-Pad55)") (class "Default")
      (node (ref "U$1") (pin "55") (pinfunction "55_55") (pintype "bidirectional"))
    )
    (net (code "158") (name "unconnected-(U$1-Pad56)") (class "Default")
      (node (ref "U$1") (pin "56") (pinfunction "56_56") (pintype "bidirectional"))
    )
    (net (code "159") (name "unconnected-(U$1-Pad60)") (class "Default")
      (node (ref "U$1") (pin "60") (pinfunction "60_60") (pintype "bidirectional"))
    )
    (net (code "160") (name "unconnected-(U$1-Pad62)") (class "Default")
      (node (ref "U$1") (pin "62") (pinfunction "62_62") (pintype "bidirectional"))
    )
    (net (code "161") (name "unconnected-(U$1-Pad64)") (class "Default")
      (node (ref "U$1") (pin "64") (pinfunction "64_64") (pintype "bidirectional"))
    )
    (net (code "162") (name "unconnected-(U$1-Pad69)") (class "Default")
      (node (ref "U$1") (pin "69") (pinfunction "69_69") (pintype "bidirectional"))
    )
    (net (code "163") (name "unconnected-(U$1-Pad70)") (class "Default")
      (node (ref "U$1") (pin "70") (pinfunction "70_70") (pintype "bidirectional"))
    )
    (net (code "164") (name "unconnected-(U$1-Pad72)") (class "Default")
      (node (ref "U$1") (pin "72") (pinfunction "72_72") (pintype "bidirectional"))
    )
    (net (code "165") (name "unconnected-(U$1-Pad73)") (class "Default")
      (node (ref "U$1") (pin "73") (pinfunction "73_73") (pintype "bidirectional"))
    )
    (net (code "166") (name "unconnected-(U$1-Pad74)") (class "Default")
      (node (ref "U$1") (pin "74") (pinfunction "74_74") (pintype "bidirectional"))
    )
    (net (code "167") (name "unconnected-(U$1-Pad75)") (class "Default")
      (node (ref "U$1") (pin "75") (pinfunction "75_75") (pintype "bidirectional"))
    )
    (net (code "168") (name "unconnected-(U$2-NC-Pad2)") (class "Default")
      (node (ref "U$2") (pin "2") (pinfunction "NC_2") (pintype "bidirectional"))
    )
    (net (code "169") (name "unconnected-(U$2-NC1-Pad5)") (class "Default")
      (node (ref "U$2") (pin "5") (pinfunction "NC1_5") (pintype "bidirectional"))
    )
    (net (code "170") (name "unconnected-(U$2-NC2-Pad7)") (class "Default")
      (node (ref "U$2") (pin "7") (pinfunction "NC2_7") (pintype "bidirectional"))
    )
    (net (code "171") (name "unconnected-(U$3-NC-Pad2)") (class "Default")
      (node (ref "U$3") (pin "2") (pinfunction "NC_2") (pintype "bidirectional"))
    )
    (net (code "172") (name "unconnected-(U$3-NC1-Pad5)") (class "Default")
      (node (ref "U$3") (pin "5") (pinfunction "NC1_5") (pintype "bidirectional"))
    )
    (net (code "173") (name "unconnected-(U$3-NC2-Pad7)") (class "Default")
      (node (ref "U$3") (pin "7") (pinfunction "NC2_7") (pintype "bidirectional"))
    )
    (net (code "174") (name "unconnected-(U$4-NC-Pad2)") (class "Default")
      (node (ref "U$4") (pin "2") (pinfunction "NC_2") (pintype "bidirectional"))
    )
    (net (code "175") (name "unconnected-(U$4-NC1-Pad5)") (class "Default")
      (node (ref "U$4") (pin "5") (pinfunction "NC1_5") (pintype "bidirectional"))
    )
    (net (code "176") (name "unconnected-(U$4-NC2-Pad7)") (class "Default")
      (node (ref "U$4") (pin "7") (pinfunction "NC2_7") (pintype "bidirectional"))
    )
    (net (code "177") (name "unconnected-(U$5-NC-Pad2)") (class "Default")
      (node (ref "U$5") (pin "2") (pinfunction "NC_2") (pintype "bidirectional"))
    )
    (net (code "178") (name "unconnected-(U$5-NC1-Pad5)") (class "Default")
      (node (ref "U$5") (pin "5") (pinfunction "NC1_5") (pintype "bidirectional"))
    )
    (net (code "179") (name "unconnected-(U$5-NC2-Pad7)") (class "Default")
      (node (ref "U$5") (pin "7") (pinfunction "NC2_7") (pintype "bidirectional"))
    )
    (net (code "180") (name "unconnected-(U$11-LBO-Pad22)") (class "Default")
      (node (ref "U$11") (pin "22") (pinfunction "LBO_22") (pintype "bidirectional"))
    )
    (net (code "181") (name "unconnected-(U$11-VREF-Pad3)") (class "Default")
      (node (ref "U$11") (pin "3") (pinfunction "VREF_3") (pintype "bidirectional"))
    )
    (net (code "182") (name "unconnected-(U$16-OC-Pad5)") (class "Default")
      (node (ref "U$16") (pin "5") (pinfunction "OC_5") (pintype "bidirectional"))
    )
    (net (code "183") (name "unconnected-(U$17-OC-Pad5)") (class "Default")
      (node (ref "U$17") (pin "5") (pinfunction "OC_5") (pintype "bidirectional"))
    )
    (net (code "184") (name "unconnected-(U$18-OC-Pad5)") (class "Default")
      (node (ref "U$18") (pin "5") (pinfunction "OC_5") (pintype "bidirectional"))
    )
    (net (code "185") (name "unconnected-(U$19-NC1-Pad1)") (class "Default")
      (node (ref "U$19") (pin "1") (pinfunction "NC1_1") (pintype "bidirectional"))
    )
    (net (code "186") (name "unconnected-(U$19-NC2-Pad5)") (class "Default")
      (node (ref "U$19") (pin "5") (pinfunction "NC2_5") (pintype "bidirectional"))
    )
    (net (code "187") (name "unconnected-(U$19-NC3-Pad6)") (class "Default")
      (node (ref "U$19") (pin "6") (pinfunction "NC3_6") (pintype "bidirectional"))
    )
    (net (code "188") (name "unconnected-(U$20-NC1-Pad1)") (class "Default")
      (node (ref "U$20") (pin "1") (pinfunction "NC1_1") (pintype "bidirectional"))
    )
    (net (code "189") (name "unconnected-(U$20-NC2-Pad5)") (class "Default")
      (node (ref "U$20") (pin "5") (pinfunction "NC2_5") (pintype "bidirectional"))
    )
    (net (code "190") (name "unconnected-(U$20-NC3-Pad6)") (class "Default")
      (node (ref "U$20") (pin "6") (pinfunction "NC3_6") (pintype "bidirectional"))
    )
  )
)
